# EEZ_DIB_MCU_r1B4.net
KiCad netlist of a schematic drawn in EAGLE
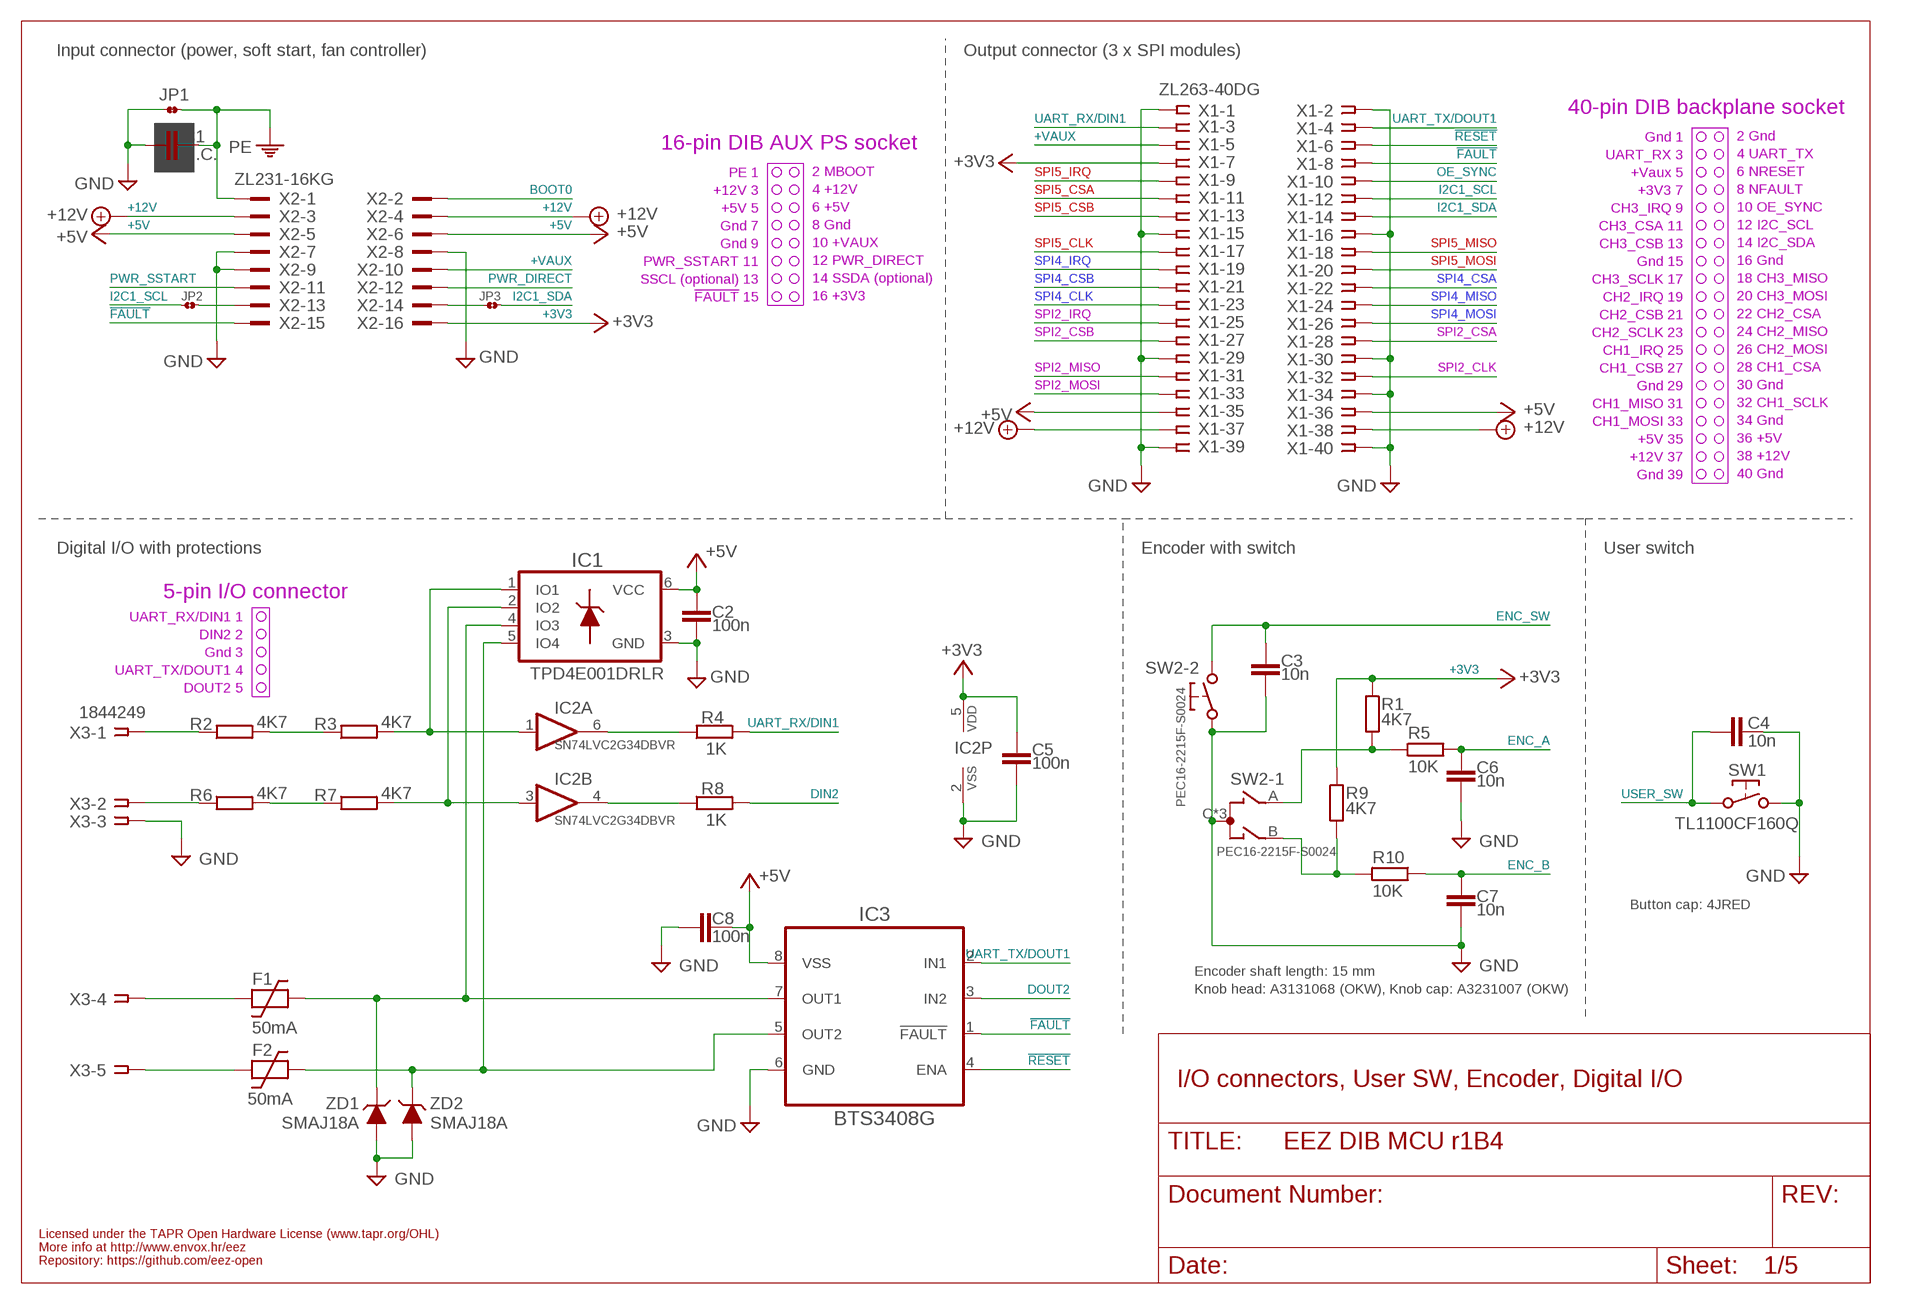
[diagram p0: schematic, sheet 1]
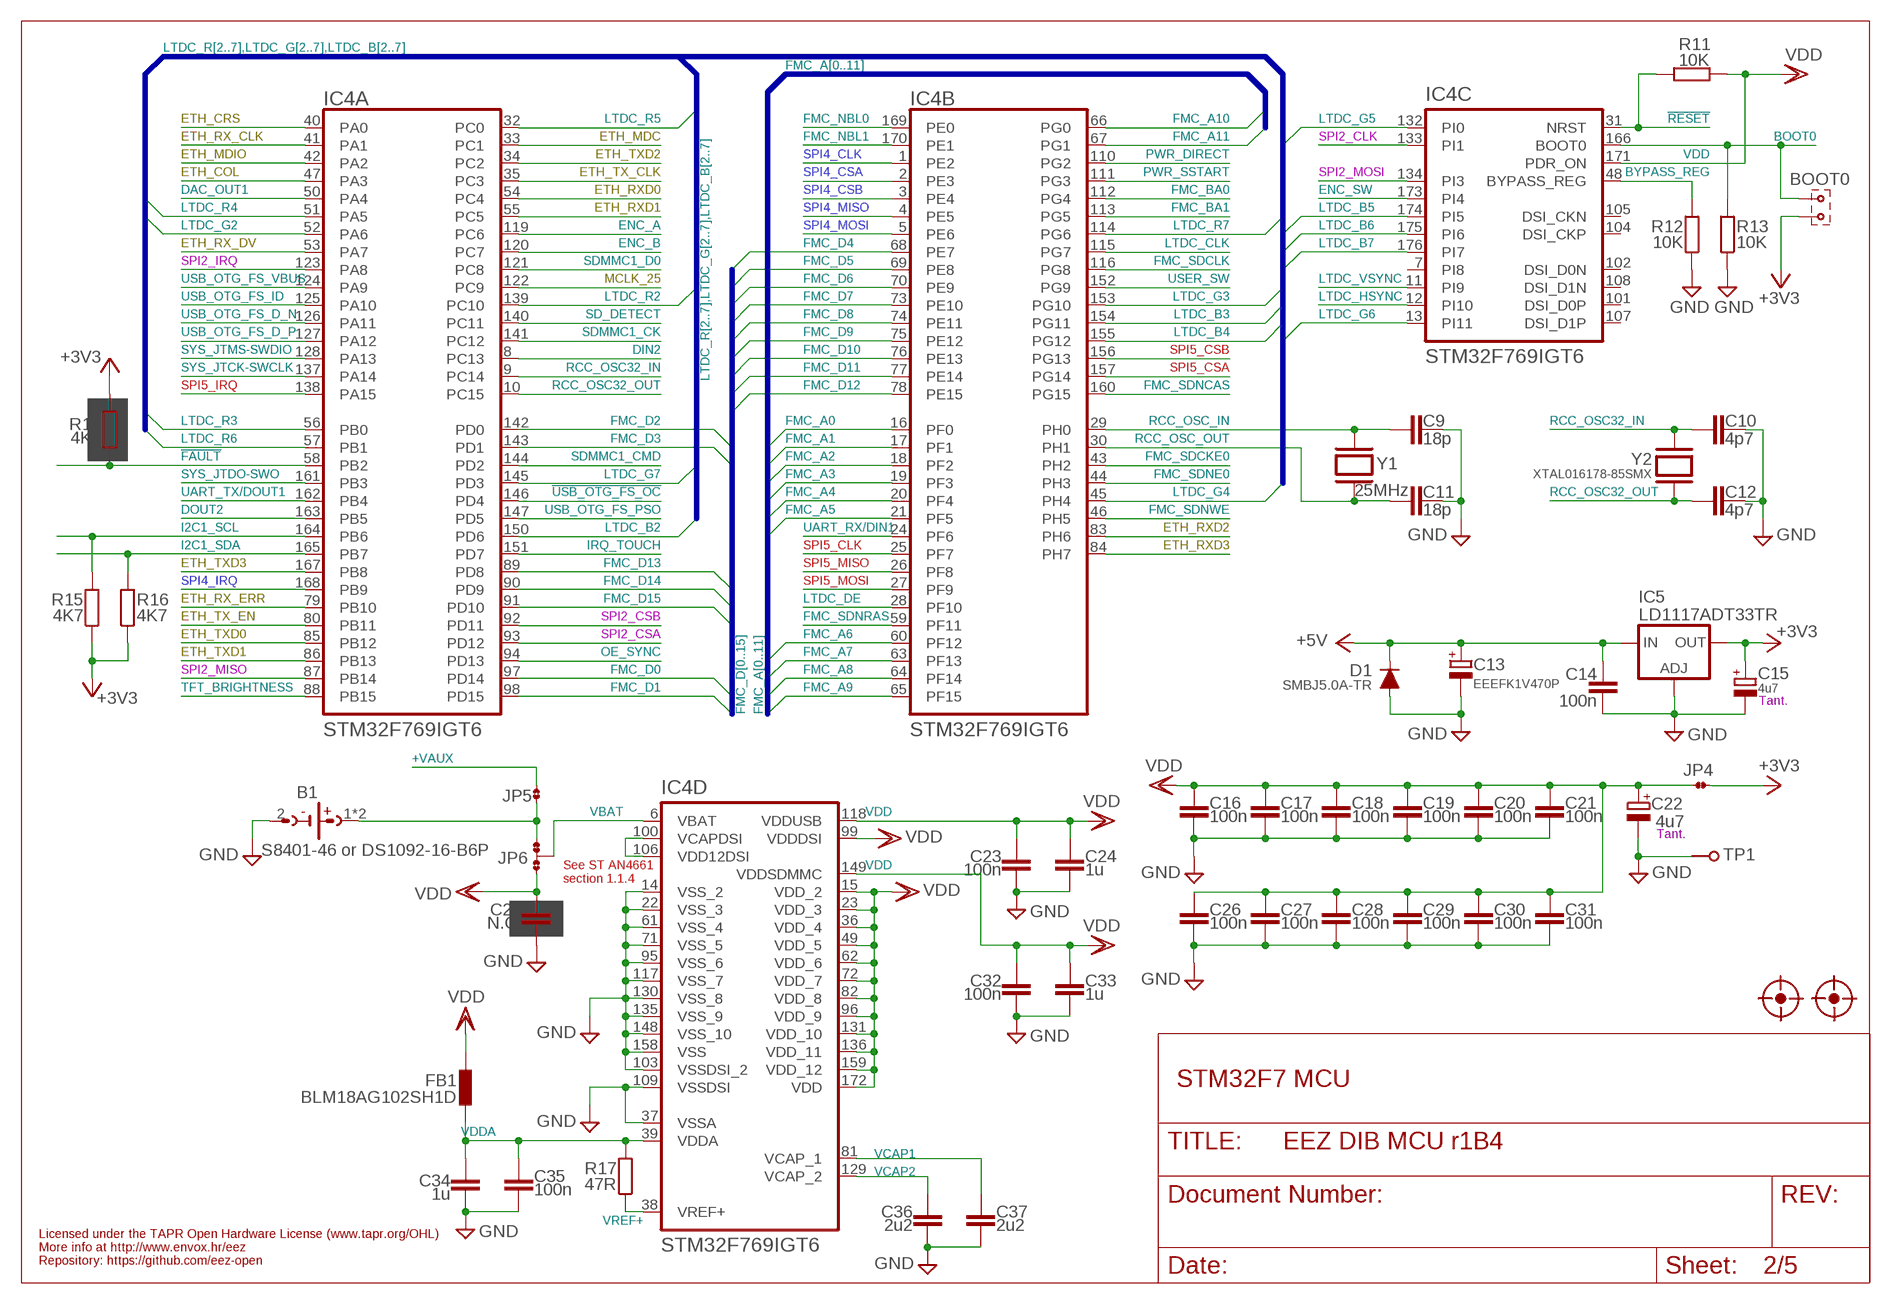
[diagram p1: schematic, sheet 2]
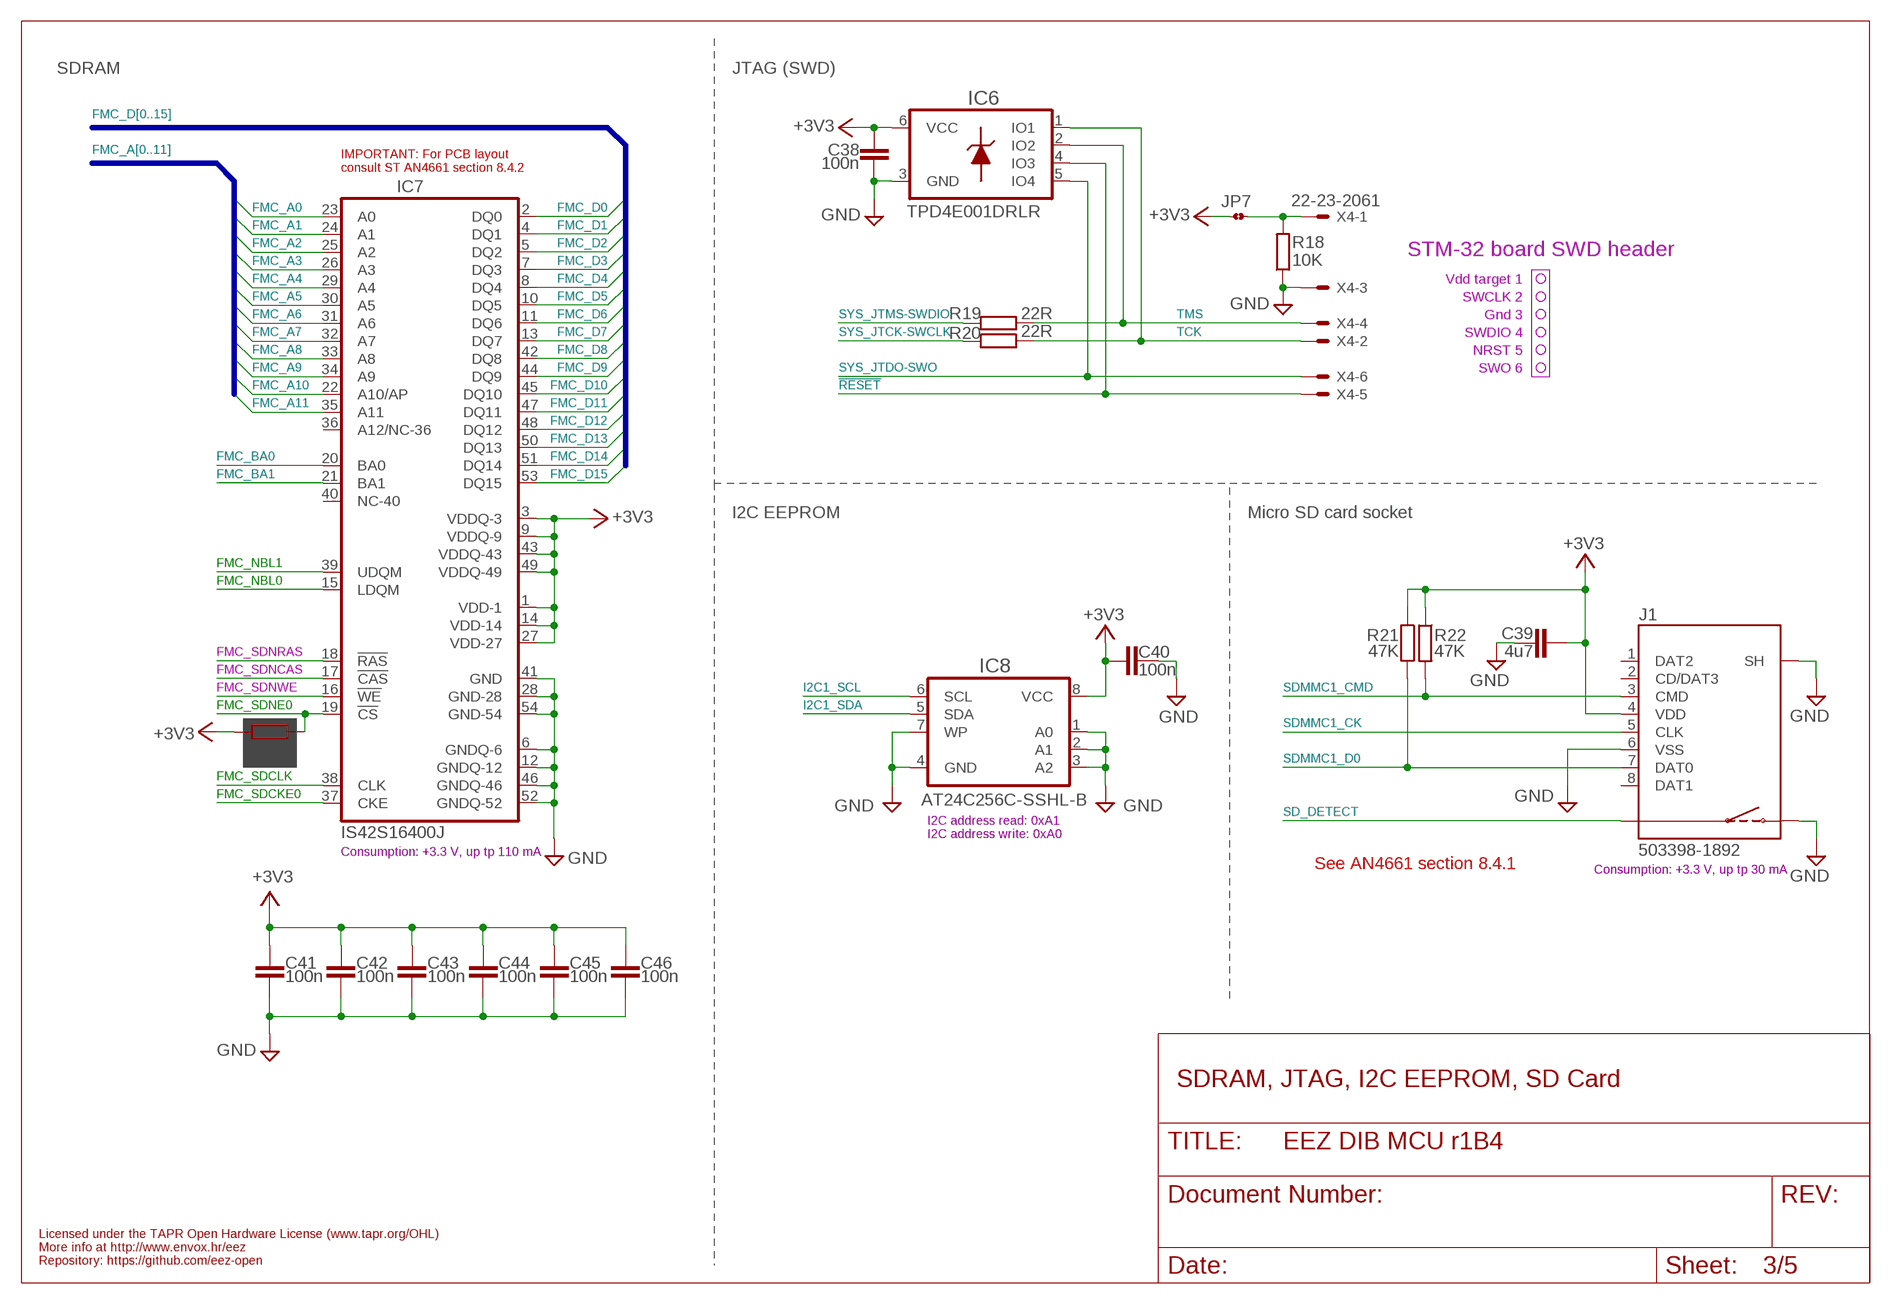
[diagram p2: schematic, sheet 3]
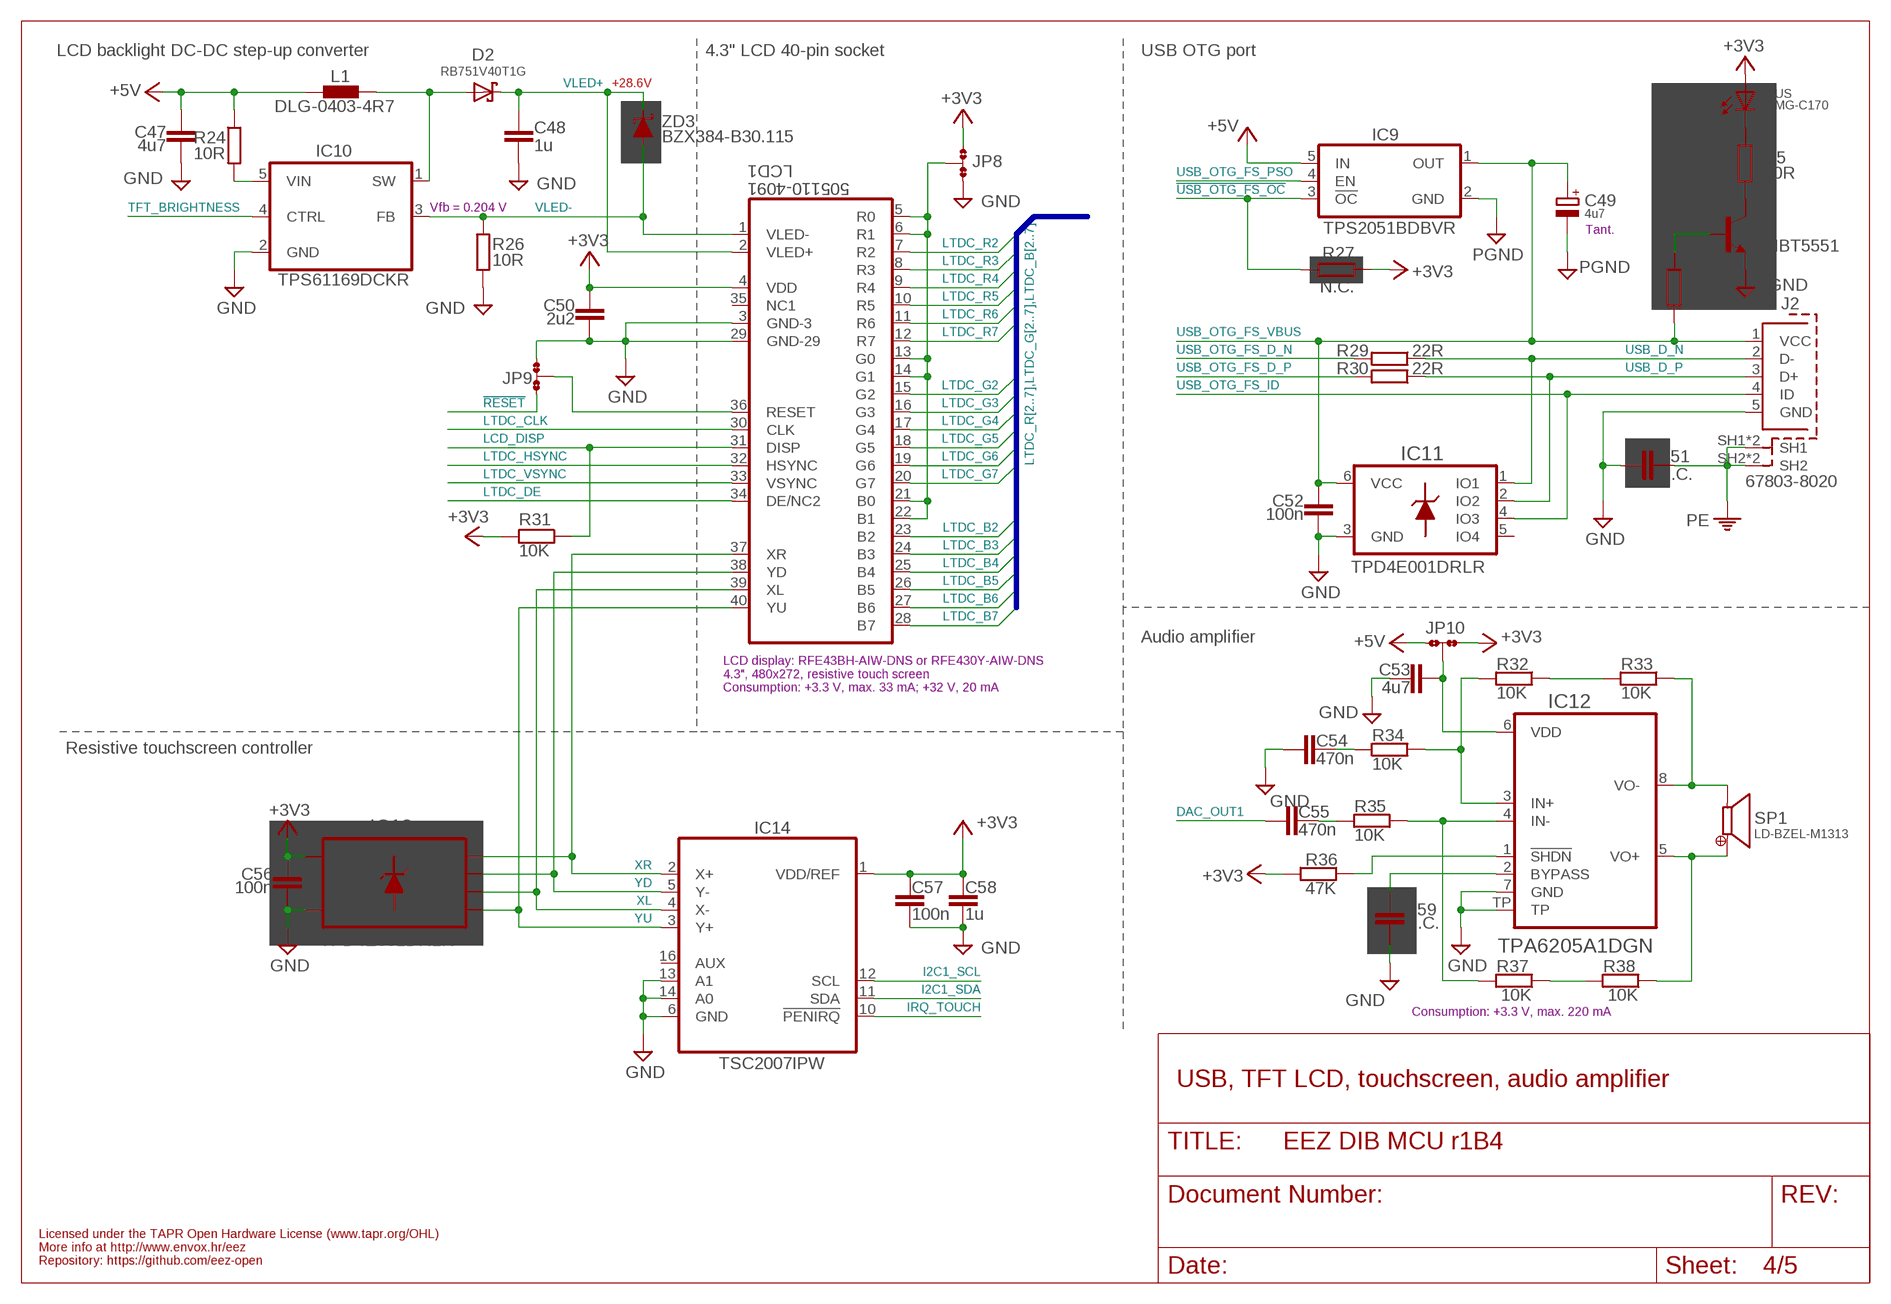
[diagram p3: schematic, sheet 4]
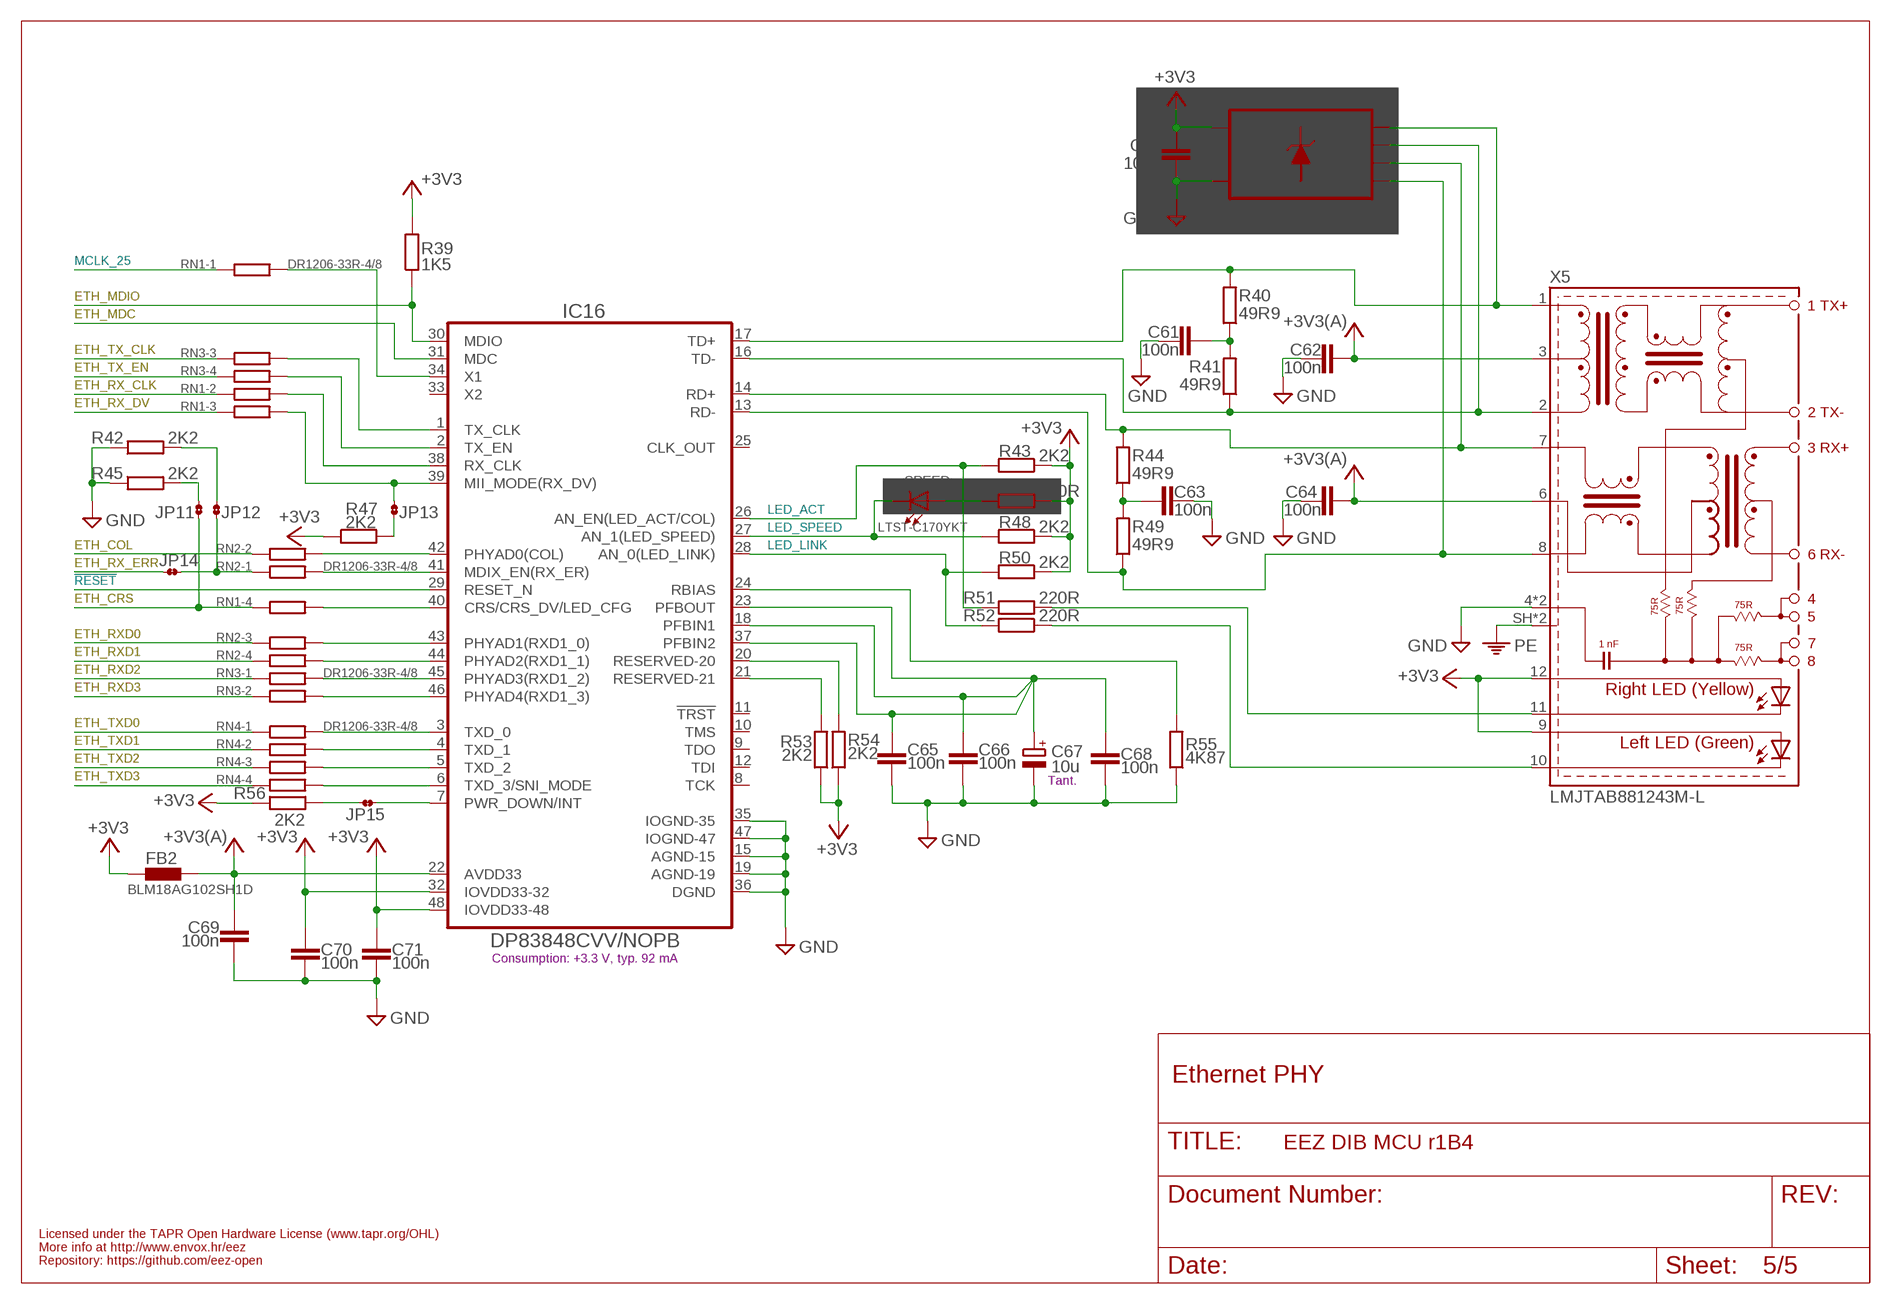
[diagram p4: schematic, sheet 5]

(export (version "E")
  (design (tool "Eeschema 10.0.6"))
  (components
    (comp (ref "C38")
      (value "100n")
      (footprint "eagle-import:C0603")
      (libsource (lib "eagle-import") (part "C-EUC0603"))
    )
    (comp (ref "C39")
      (value "4u7")
      (footprint "eagle-import:C1206")
      (libsource (lib "eagle-import") (part "C-EUC1206"))
    )
    (comp (ref "C40")
      (value "100n")
      (footprint "eagle-import:C0603")
      (libsource (lib "eagle-import") (part "C-EUC0603"))
    )
    (comp (ref "C41")
      (value "100n")
      (footprint "eagle-import:C0603")
      (libsource (lib "eagle-import") (part "C-EUC0603"))
    )
    (comp (ref "C42")
      (value "100n")
      (footprint "eagle-import:C0603")
      (libsource (lib "eagle-import") (part "C-EUC0603"))
    )
    (comp (ref "C43")
      (value "100n")
      (footprint "eagle-import:C0603")
      (libsource (lib "eagle-import") (part "C-EUC0603"))
    )
    (comp (ref "C44")
      (value "100n")
      (footprint "eagle-import:C0603")
      (libsource (lib "eagle-import") (part "C-EUC0603"))
    )
    (comp (ref "C45")
      (value "100n")
      (footprint "eagle-import:C0603")
      (libsource (lib "eagle-import") (part "C-EUC0603"))
    )
    (comp (ref "C46")
      (value "100n")
      (footprint "eagle-import:C0603")
      (libsource (lib "eagle-import") (part "C-EUC0603"))
    )
    (comp (ref "IC6")
      (value "TPD4E001DRLR")
      (footprint "eagle-import:DRL6")
      (libsource (lib "eagle-import") (part "TPD4E001-DRL"))
    )
    (comp (ref "IC7")
      (value "IS42S16400J")
      (footprint "eagle-import:TSOPII-54")
      (libsource (lib "eagle-import") (part "IS42S16400"))
    )
    (comp (ref "IC8")
      (value "AT24C256C-SSHL-B")
      (footprint "eagle-import:SOIC127P600X173-8N")
      (libsource (lib "eagle-import") (part "AT24CXXSOIC8"))
    )
    (comp (ref "J1")
      (value "503398-1892")
      (footprint "eagle-import:5033981892")
      (libsource (lib "eagle-import") (part "5033981892"))
    )
    (comp (ref "JP7")
      (value "JP2-CUT")
      (footprint "eagle-import:JP2-CUT")
      (libsource (lib "eagle-import") (part "JP2-CUT"))
    )
    (comp (ref "R18")
      (value "10K")
      (footprint "eagle-import:R0805")
      (libsource (lib "eagle-import") (part "R-EU_R0805"))
    )
    (comp (ref "R19")
      (value "22R")
      (footprint "eagle-import:R0805")
      (libsource (lib "eagle-import") (part "R-EU_R0805"))
    )
    (comp (ref "R20")
      (value "22R")
      (footprint "eagle-import:R0805")
      (libsource (lib "eagle-import") (part "R-EU_R0805"))
    )
    (comp (ref "R21")
      (value "47K")
      (footprint "eagle-import:R0805")
      (libsource (lib "eagle-import") (part "R-EU_R0805"))
    )
    (comp (ref "R22")
      (value "47K")
      (footprint "eagle-import:R0805")
      (libsource (lib "eagle-import") (part "R-EU_R0805"))
    )
    (comp (ref "R23")
      (value "N.C.")
      (footprint "eagle-import:R0805")
      (libsource (lib "eagle-import") (part "R-EU_R0805"))
    )
    (comp (ref "X4")
      (value "22-23-2061")
      (footprint "eagle-import:22-23-2061")
      (fields (field (name "MF") "MOLEX"))
      (libsource (lib "eagle-import") (part "22-23-2061"))
    )
    (comp (ref "B1")
      (value "S8401-46 or DS1092-16-B6P")
      (footprint "eagle-import:S8401-46")
      (libsource (lib "eagle-import") (part "CELL_BATTERYVERT"))
    )
    (comp (ref "BOOT0")
      (value "JUMPER-2PIN-2MM")
      (footprint "eagle-import:2MM-2")
      (libsource (lib "eagle-import") (part "JUMPER-2PIN-2MM"))
    )
    (comp (ref "C9")
      (value "18p")
      (footprint "eagle-import:C0603")
      (libsource (lib "eagle-import") (part "C-EUC0603"))
    )
    (comp (ref "C10")
      (value "4p7")
      (footprint "eagle-import:C0603")
      (libsource (lib "eagle-import") (part "C-EUC0603"))
    )
    (comp (ref "C11")
      (value "18p")
      (footprint "eagle-import:C0603")
      (libsource (lib "eagle-import") (part "C-EUC0603"))
    )
    (comp (ref "C12")
      (value "4p7")
      (footprint "eagle-import:C0603")
      (libsource (lib "eagle-import") (part "C-EUC0603"))
    )
    (comp (ref "C13")
      (value "EEEFK1V470P")
      (footprint "eagle-import:CAPAE660X610N")
      (libsource (lib "eagle-import") (part "ECAPPANASONIC_H"))
    )
    (comp (ref "C14")
      (value "100n")
      (footprint "eagle-import:C0603")
      (libsource (lib "eagle-import") (part "C-EUC0603"))
    )
    (comp (ref "C15")
      (value "4u7")
      (footprint "eagle-import:EC1206")
      (libsource (lib "eagle-import") (part "ECAP1206"))
    )
    (comp (ref "C16")
      (value "100n")
      (footprint "eagle-import:C0603")
      (libsource (lib "eagle-import") (part "C-EUC0603"))
    )
    (comp (ref "C17")
      (value "100n")
      (footprint "eagle-import:C0603")
      (libsource (lib "eagle-import") (part "C-EUC0603"))
    )
    (comp (ref "C18")
      (value "100n")
      (footprint "eagle-import:C0603")
      (libsource (lib "eagle-import") (part "C-EUC0603"))
    )
    (comp (ref "C19")
      (value "100n")
      (footprint "eagle-import:C0603")
      (libsource (lib "eagle-import") (part "C-EUC0603"))
    )
    (comp (ref "C20")
      (value "100n")
      (footprint "eagle-import:C0603")
      (libsource (lib "eagle-import") (part "C-EUC0603"))
    )
    (comp (ref "C21")
      (value "100n")
      (footprint "eagle-import:C0603")
      (libsource (lib "eagle-import") (part "C-EUC0603"))
    )
    (comp (ref "C22")
      (value "4u7")
      (footprint "eagle-import:EC1206")
      (libsource (lib "eagle-import") (part "ECAP1206"))
    )
    (comp (ref "C23")
      (value "100n")
      (footprint "eagle-import:C0603")
      (libsource (lib "eagle-import") (part "C-EUC0603"))
    )
    (comp (ref "C24")
      (value "1u")
      (footprint "eagle-import:C0805")
      (libsource (lib "eagle-import") (part "C-EUC0805"))
    )
    (comp (ref "C25")
      (value "N.C.")
      (footprint "eagle-import:C0603")
      (libsource (lib "eagle-import") (part "C-EUC0603"))
    )
    (comp (ref "C26")
      (value "100n")
      (footprint "eagle-import:C0603")
      (libsource (lib "eagle-import") (part "C-EUC0603"))
    )
    (comp (ref "C27")
      (value "100n")
      (footprint "eagle-import:C0603")
      (libsource (lib "eagle-import") (part "C-EUC0603"))
    )
    (comp (ref "C28")
      (value "100n")
      (footprint "eagle-import:C0603")
      (libsource (lib "eagle-import") (part "C-EUC0603"))
    )
    (comp (ref "C29")
      (value "100n")
      (footprint "eagle-import:C0603")
      (libsource (lib "eagle-import") (part "C-EUC0603"))
    )
    (comp (ref "C30")
      (value "100n")
      (footprint "eagle-import:C0603")
      (libsource (lib "eagle-import") (part "C-EUC0603"))
    )
    (comp (ref "C31")
      (value "100n")
      (footprint "eagle-import:C0603")
      (libsource (lib "eagle-import") (part "C-EUC0603"))
    )
    (comp (ref "C32")
      (value "100n")
      (footprint "eagle-import:C0603")
      (libsource (lib "eagle-import") (part "C-EUC0603"))
    )
    (comp (ref "C33")
      (value "1u")
      (footprint "eagle-import:C0805")
      (libsource (lib "eagle-import") (part "C-EUC0805"))
    )
    (comp (ref "C34")
      (value "1u")
      (footprint "eagle-import:C0805")
      (libsource (lib "eagle-import") (part "C-EUC0805"))
    )
    (comp (ref "C35")
      (value "100n")
      (footprint "eagle-import:C0603")
      (libsource (lib "eagle-import") (part "C-EUC0603"))
    )
    (comp (ref "C36")
      (value "2u2")
      (footprint "eagle-import:C0805")
      (libsource (lib "eagle-import") (part "C-EUC0805"))
    )
    (comp (ref "C37")
      (value "2u2")
      (footprint "eagle-import:C0805")
      (libsource (lib "eagle-import") (part "C-EUC0805"))
    )
    (comp (ref "D1")
      (value "SMBJ5.0A-TR")
      (footprint "eagle-import:DO214AA")
      (libsource (lib "eagle-import") (part "DIODEDO214AA"))
    )
    (comp (ref "FB1")
      (value "BLM18AG102SH1D")
      (footprint "eagle-import:BEAD0603")
      (libsource (lib "eagle-import") (part "FERRITE_BEAD0603"))
    )
    (comp (ref "FM1")
      (value "FIDUCIAL")
      (footprint "eagle-import:FIDUCIAL")
      (libsource (lib "eagle-import") (part "FIDUCIAL"))
    )
    (comp (ref "FM2")
      (value "FIDUCIAL")
      (footprint "eagle-import:FIDUCIAL")
      (libsource (lib "eagle-import") (part "FIDUCIAL"))
    )
    (comp (ref "IC4")
      (value "STM32F769IGT6")
      (footprint "eagle-import:LQFP-176_24X24MM")
      (fields
        (field (name "MANUFACTURER_PART_NUMBER") "stm32f769ixt")
        (field (name "COPYRIGHT") "Copyright C 2016 Accelerated Designs. All rights reserved")
      )
      (libsource (lib "eagle-import") (part "STM32F769IXT"))
    )
    (comp (ref "IC5")
      (value "LD1117ADT33TR")
      (footprint "eagle-import:DPACK")
      (libsource (lib "eagle-import") (part "LD117A?DT33TR"))
    )
    (comp (ref "JP4")
      (value "JP2-NOCUT")
      (footprint "eagle-import:JP2-NOCUT")
      (libsource (lib "eagle-import") (part "JP2-NOCUT"))
    )
    (comp (ref "JP5")
      (value "JP2-CUT")
      (footprint "eagle-import:JP2-CUT")
      (libsource (lib "eagle-import") (part "JP2-CUT"))
    )
    (comp (ref "JP6")
      (value "JP3-CUT")
      (footprint "eagle-import:JP3-CUT")
      (libsource (lib "eagle-import") (part "JP3-CUT"))
    )
    (comp (ref "R11")
      (value "10K")
      (footprint "eagle-import:R0805")
      (libsource (lib "eagle-import") (part "R-EU_R0805"))
    )
    (comp (ref "R12")
      (value "10K")
      (footprint "eagle-import:R0805")
      (libsource (lib "eagle-import") (part "R-EU_R0805"))
    )
    (comp (ref "R13")
      (value "10K")
      (footprint "eagle-import:R0805")
      (libsource (lib "eagle-import") (part "R-EU_R0805"))
    )
    (comp (ref "R14")
      (value "4K7")
      (footprint "eagle-import:R0805")
      (libsource (lib "eagle-import") (part "R-EU_R0805"))
    )
    (comp (ref "R15")
      (value "4K7")
      (footprint "eagle-import:R0805")
      (libsource (lib "eagle-import") (part "R-EU_R0805"))
    )
    (comp (ref "R16")
      (value "4K7")
      (footprint "eagle-import:R0805")
      (libsource (lib "eagle-import") (part "R-EU_R0805"))
    )
    (comp (ref "R17")
      (value "47R")
      (footprint "eagle-import:R0805")
      (libsource (lib "eagle-import") (part "R-EU_R0805"))
    )
    (comp (ref "TP1")
      (value "PCB_TEST_TABSHIELD")
      (footprint "eagle-import:PCB_SHIELD_TAB")
      (libsource (lib "eagle-import") (part "PCB_TEST_TABSHIELD"))
    )
    (comp (ref "Y1")
      (value "25MHz")
      (footprint "eagle-import:HC-49_4H")
      (libsource (lib "eagle-import") (part "XTALSMD"))
    )
    (comp (ref "Y2")
      (value "XTAL016178-85SMX")
      (footprint "eagle-import:85SMX")
      (libsource (lib "eagle-import") (part "XTAL85SMX"))
    )
    (comp (ref "C60")
      (value "100n")
      (footprint "eagle-import:C0603")
      (libsource (lib "eagle-import") (part "C-EUC0603"))
    )
    (comp (ref "C61")
      (value "100n")
      (footprint "eagle-import:C0603")
      (libsource (lib "eagle-import") (part "C-EUC0603"))
    )
    (comp (ref "C62")
      (value "100n")
      (footprint "eagle-import:C0603")
      (libsource (lib "eagle-import") (part "C-EUC0603"))
    )
    (comp (ref "C63")
      (value "100n")
      (footprint "eagle-import:C0603")
      (libsource (lib "eagle-import") (part "C-EUC0603"))
    )
    (comp (ref "C64")
      (value "100n")
      (footprint "eagle-import:C0603")
      (libsource (lib "eagle-import") (part "C-EUC0603"))
    )
    (comp (ref "C65")
      (value "100n")
      (footprint "eagle-import:C0603")
      (libsource (lib "eagle-import") (part "C-EUC0603"))
    )
    (comp (ref "C66")
      (value "100n")
      (footprint "eagle-import:C0603")
      (libsource (lib "eagle-import") (part "C-EUC0603"))
    )
    (comp (ref "C67")
      (value "10u")
      (footprint "eagle-import:EC1206")
      (libsource (lib "eagle-import") (part "ECAP1206"))
    )
    (comp (ref "C68")
      (value "100n")
      (footprint "eagle-import:C0603")
      (libsource (lib "eagle-import") (part "C-EUC0603"))
    )
    (comp (ref "C69")
      (value "100n")
      (footprint "eagle-import:C0603")
      (libsource (lib "eagle-import") (part "C-EUC0603"))
    )
    (comp (ref "C70")
      (value "100n")
      (footprint "eagle-import:C0603")
      (libsource (lib "eagle-import") (part "C-EUC0603"))
    )
    (comp (ref "C71")
      (value "100n")
      (footprint "eagle-import:C0603")
      (libsource (lib "eagle-import") (part "C-EUC0603"))
    )
    (comp (ref "FB2")
      (value "BLM18AG102SH1D")
      (footprint "eagle-import:BEAD0603")
      (libsource (lib "eagle-import") (part "FERRITE_BEAD0603"))
    )
    (comp (ref "IC15")
      (value "TPD4E001DRLR")
      (footprint "eagle-import:DRL6")
      (libsource (lib "eagle-import") (part "TPD4E001-DRL"))
    )
    (comp (ref "IC16")
      (value "DP83848CVV/NOPB")
      (footprint "eagle-import:PT48")
      (libsource (lib "eagle-import") (part "DP83848CVV/NOPB"))
    )
    (comp (ref "JP11")
      (value "JP2-CUT")
      (footprint "eagle-import:JP2-CUT")
      (libsource (lib "eagle-import") (part "JP2-CUT"))
    )
    (comp (ref "JP12")
      (value "JP2-CUT")
      (footprint "eagle-import:JP2-CUT")
      (libsource (lib "eagle-import") (part "JP2-CUT"))
    )
    (comp (ref "JP13")
      (value "JP2-CUT")
      (footprint "eagle-import:JP2-CUT")
      (libsource (lib "eagle-import") (part "JP2-CUT"))
    )
    (comp (ref "JP14")
      (value "JP2-NOCUT")
      (footprint "eagle-import:JP2-NOCUT")
      (libsource (lib "eagle-import") (part "JP2-NOCUT"))
    )
    (comp (ref "JP15")
      (value "JP2-NOCUT")
      (footprint "eagle-import:JP2-NOCUT")
      (libsource (lib "eagle-import") (part "JP2-NOCUT"))
    )
    (comp (ref "R39")
      (value "1K5")
      (footprint "eagle-import:R0805")
      (libsource (lib "eagle-import") (part "R-EU_R0805"))
    )
    (comp (ref "R40")
      (value "49R9")
      (footprint "eagle-import:R0805")
      (libsource (lib "eagle-import") (part "R-EU_R0805"))
    )
    (comp (ref "R41")
      (value "49R9")
      (footprint "eagle-import:R0805")
      (libsource (lib "eagle-import") (part "R-EU_R0805"))
    )
    (comp (ref "R42")
      (value "2K2")
      (footprint "eagle-import:R0805")
      (libsource (lib "eagle-import") (part "R-EU_R0805"))
    )
    (comp (ref "R43")
      (value "2K2")
      (footprint "eagle-import:R0805")
      (libsource (lib "eagle-import") (part "R-EU_R0805"))
    )
    (comp (ref "R44")
      (value "49R9")
      (footprint "eagle-import:R0805")
      (libsource (lib "eagle-import") (part "R-EU_R0805"))
    )
    (comp (ref "R45")
      (value "2K2")
      (footprint "eagle-import:R0805")
      (libsource (lib "eagle-import") (part "R-EU_R0805"))
    )
    (comp (ref "R46")
      (value "220R")
      (footprint "eagle-import:R0805")
      (libsource (lib "eagle-import") (part "R-EU_R0805"))
    )
    (comp (ref "R47")
      (value "2K2")
      (footprint "eagle-import:R0805")
      (libsource (lib "eagle-import") (part "R-EU_R0805"))
    )
    (comp (ref "R48")
      (value "2K2")
      (footprint "eagle-import:R0805")
      (libsource (lib "eagle-import") (part "R-EU_R0805"))
    )
    (comp (ref "R49")
      (value "49R9")
      (footprint "eagle-import:R0805")
      (libsource (lib "eagle-import") (part "R-EU_R0805"))
    )
    (comp (ref "R50")
      (value "2K2")
      (footprint "eagle-import:R0805")
      (libsource (lib "eagle-import") (part "R-EU_R0805"))
    )
    (comp (ref "R51")
      (value "220R")
      (footprint "eagle-import:R0805")
      (libsource (lib "eagle-import") (part "R-EU_R0805"))
    )
    (comp (ref "R52")
      (value "220R")
      (footprint "eagle-import:R0805")
      (libsource (lib "eagle-import") (part "R-EU_R0805"))
    )
    (comp (ref "R53")
      (value "2K2")
      (footprint "eagle-import:R0805")
      (libsource (lib "eagle-import") (part "R-EU_R0805"))
    )
    (comp (ref "R54")
      (value "2K2")
      (footprint "eagle-import:R0805")
      (libsource (lib "eagle-import") (part "R-EU_R0805"))
    )
    (comp (ref "R55")
      (value "4K87")
      (footprint "eagle-import:R0805")
      (libsource (lib "eagle-import") (part "R-EU_R0805"))
    )
    (comp (ref "R56")
      (value "2K2")
      (footprint "eagle-import:R0805")
      (libsource (lib "eagle-import") (part "R-EU_R0805"))
    )
    (comp (ref "RN1")
      (value "DR1206-33R-4/8")
      (footprint "eagle-import:CAY16")
      (libsource (lib "eagle-import") (part "R_ARRAY4"))
    )
    (comp (ref "RN2")
      (value "DR1206-33R-4/8")
      (footprint "eagle-import:CAY16")
      (libsource (lib "eagle-import") (part "R_ARRAY4"))
    )
    (comp (ref "RN3")
      (value "DR1206-33R-4/8")
      (footprint "eagle-import:CAY16")
      (libsource (lib "eagle-import") (part "R_ARRAY4"))
    )
    (comp (ref "RN4")
      (value "DR1206-33R-4/8")
      (footprint "eagle-import:CAY16")
      (libsource (lib "eagle-import") (part "R_ARRAY4"))
    )
    (comp (ref "SPEED")
      (value "LTST-C170YKT")
      (footprint "eagle-import:LED_0805")
      (libsource (lib "eagle-import") (part "LED0805"))
    )
    (comp (ref "X5")
      (value "LMJTAB881243M-L")
      (footprint "eagle-import:RJ45-TRAFO-LED")
      (libsource (lib "eagle-import") (part "RJ45-TRAFO-LED"))
    )
    (comp (ref "C47")
      (value "4u7")
      (footprint "eagle-import:C1206")
      (libsource (lib "eagle-import") (part "C-EUC1206"))
    )
    (comp (ref "C48")
      (value "1u")
      (footprint "eagle-import:C0805")
      (libsource (lib "eagle-import") (part "C-EUC0805"))
    )
    (comp (ref "C49")
      (value "4u7")
      (footprint "eagle-import:EC1206")
      (libsource (lib "eagle-import") (part "ECAP1206"))
    )
    (comp (ref "C50")
      (value "2u2")
      (footprint "eagle-import:C0805")
      (libsource (lib "eagle-import") (part "C-EUC0805"))
    )
    (comp (ref "C51")
      (value "N.C.")
      (footprint "eagle-import:C1210")
      (libsource (lib "eagle-import") (part "C-EUC1210"))
    )
    (comp (ref "C52")
      (value "100n")
      (footprint "eagle-import:C0603")
      (libsource (lib "eagle-import") (part "C-EUC0603"))
    )
    (comp (ref "C53")
      (value "4u7")
      (footprint "eagle-import:C1206")
      (libsource (lib "eagle-import") (part "C-EUC1206"))
    )
    (comp (ref "C54")
      (value "470n")
      (footprint "eagle-import:C0805")
      (libsource (lib "eagle-import") (part "C-EUC0805"))
    )
    (comp (ref "C55")
      (value "470n")
      (footprint "eagle-import:C0805")
      (libsource (lib "eagle-import") (part "C-EUC0805"))
    )
    (comp (ref "C56")
      (value "100n")
      (footprint "eagle-import:C0603")
      (libsource (lib "eagle-import") (part "C-EUC0603"))
    )
    (comp (ref "C57")
      (value "100n")
      (footprint "eagle-import:C0603")
      (libsource (lib "eagle-import") (part "C-EUC0603"))
    )
    (comp (ref "C58")
      (value "1u")
      (footprint "eagle-import:C0805")
      (libsource (lib "eagle-import") (part "C-EUC0805"))
    )
    (comp (ref "C59")
      (value "N.C.")
      (footprint "eagle-import:C0805")
      (libsource (lib "eagle-import") (part "C-EUC0805"))
    )
    (comp (ref "D2")
      (value "RB751V40T1G")
      (footprint "eagle-import:SOD323-R")
      (libsource (lib "eagle-import") (part "SCHOTTKYSOD-323R"))
    )
    (comp (ref "IC9")
      (value "TPS2051BDBVR")
      (footprint "eagle-import:DBV5")
      (libsource (lib "eagle-import") (part "TPS2051B"))
    )
    (comp (ref "IC10")
      (value "TPS61169DCKR")
      (footprint "eagle-import:DCK5")
      (fields (field (name "MANUFACTURER") "Texas Instruments"))
      (libsource (lib "eagle-import") (part "TPS61169DCKR"))
    )
    (comp (ref "IC11")
      (value "TPD4E001DRLR")
      (footprint "eagle-import:DRL6")
      (libsource (lib "eagle-import") (part "TPD4E001-DRL"))
    )
    (comp (ref "IC12")
      (value "TPA6205A1DGN")
      (footprint "eagle-import:SOP65P490X110-9N")
      (libsource (lib "eagle-import") (part "TPA6205"))
    )
    (comp (ref "IC13")
      (value "TPD4E001DRLR")
      (footprint "eagle-import:DRL6")
      (libsource (lib "eagle-import") (part "TPD4E001-DRL"))
    )
    (comp (ref "IC14")
      (value "TSC2007IPW")
      (footprint "eagle-import:PW(R-PDSO-G16)")
      (libsource (lib "eagle-import") (part "TSC2007IPW"))
    )
    (comp (ref "J2")
      (value "67803-8020")
      (footprint "eagle-import:678038020")
      (libsource (lib "eagle-import") (part "678038020"))
    )
    (comp (ref "JP8")
      (value "JP3-CUT")
      (footprint "eagle-import:JP3-CUT")
      (libsource (lib "eagle-import") (part "JP3-CUT"))
    )
    (comp (ref "JP9")
      (value "JP3-CUT")
      (footprint "eagle-import:JP3-CUT")
      (libsource (lib "eagle-import") (part "JP3-CUT"))
    )
    (comp (ref "JP10")
      (value "JP3-CUT")
      (footprint "eagle-import:JP3-CUT")
      (libsource (lib "eagle-import") (part "JP3-CUT"))
    )
    (comp (ref "L1")
      (value "DLG-0403-4R7")
      (footprint "eagle-import:DE0403")
      (libsource (lib "eagle-import") (part "DE0403"))
    )
    (comp (ref "LCD1")
      (value "505110-4091")
      (footprint "eagle-import:FPC_40")
      (libsource (lib "eagle-import") (part "RFE430Y-AIW-DNS"))
    )
    (comp (ref "Q1")
      (value "MMBT5551")
      (footprint "eagle-import:SOT23-BEC")
      (libsource (lib "eagle-import") (part "-NPN-SOT23-BECMMBT5551LT1"))
    )
    (comp (ref "R24")
      (value "10R")
      (footprint "eagle-import:R0805")
      (libsource (lib "eagle-import") (part "R-EU_R0805"))
    )
    (comp (ref "R25")
      (value "330R")
      (footprint "eagle-import:R0805")
      (libsource (lib "eagle-import") (part "R-EU_R0805"))
    )
    (comp (ref "R26")
      (value "10R")
      (footprint "eagle-import:R0805")
      (libsource (lib "eagle-import") (part "R-EU_R0805"))
    )
    (comp (ref "R27")
      (value "N.C.")
      (footprint "eagle-import:R0805")
      (libsource (lib "eagle-import") (part "R-EU_R0805"))
    )
    (comp (ref "R28")
      (value "47K")
      (footprint "eagle-import:R0805")
      (libsource (lib "eagle-import") (part "R-EU_R0805"))
    )
    (comp (ref "R29")
      (value "22R")
      (footprint "eagle-import:R0805")
      (libsource (lib "eagle-import") (part "R-EU_R0805"))
    )
    (comp (ref "R30")
      (value "22R")
      (footprint "eagle-import:R0805")
      (libsource (lib "eagle-import") (part "R-EU_R0805"))
    )
    (comp (ref "R31")
      (value "10K")
      (footprint "eagle-import:R0805")
      (libsource (lib "eagle-import") (part "R-EU_R0805"))
    )
    (comp (ref "R32")
      (value "10K")
      (footprint "eagle-import:R0805")
      (libsource (lib "eagle-import") (part "R-EU_R0805"))
    )
    (comp (ref "R33")
      (value "10K")
      (footprint "eagle-import:R0805")
      (libsource (lib "eagle-import") (part "R-EU_R0805"))
    )
    (comp (ref "R34")
      (value "10K")
      (footprint "eagle-import:R0805")
      (libsource (lib "eagle-import") (part "R-EU_R0805"))
    )
    (comp (ref "R35")
      (value "10K")
      (footprint "eagle-import:R0805")
      (libsource (lib "eagle-import") (part "R-EU_R0805"))
    )
    (comp (ref "R36")
      (value "47K")
      (footprint "eagle-import:R0805")
      (libsource (lib "eagle-import") (part "R-EU_R0805"))
    )
    (comp (ref "R37")
      (value "10K")
      (footprint "eagle-import:R0805")
      (libsource (lib "eagle-import") (part "R-EU_R0805"))
    )
    (comp (ref "R38")
      (value "10K")
      (footprint "eagle-import:R0805")
      (libsource (lib "eagle-import") (part "R-EU_R0805"))
    )
    (comp (ref "SP1")
      (value "LD-BZEL-M1313")
      (footprint "eagle-import:LD-BZEL-M1313")
      (libsource (lib "eagle-import") (part "LD-BZEL-M1313"))
    )
    (comp (ref "VBUS")
      (value "HSMG-C170")
      (footprint "eagle-import:LED_0805")
      (libsource (lib "eagle-import") (part "LED0805"))
    )
    (comp (ref "ZD3")
      (value "BZX384-B30.115")
      (footprint "eagle-import:SOD323-W")
      (libsource (lib "eagle-import") (part "ZENER-DIODESOD323"))
    )
    (comp (ref "C1")
      (value "N.C.")
      (footprint "eagle-import:C1210")
      (libsource (lib "eagle-import") (part "C-EUC1210"))
    )
    (comp (ref "C2")
      (value "100n")
      (footprint "eagle-import:C0603")
      (libsource (lib "eagle-import") (part "C-EUC0603"))
    )
    (comp (ref "C3")
      (value "10n")
      (footprint "eagle-import:C0805")
      (libsource (lib "eagle-import") (part "C-EUC0805"))
    )
    (comp (ref "C4")
      (value "10n")
      (footprint "eagle-import:C0805")
      (libsource (lib "eagle-import") (part "C-EUC0805"))
    )
    (comp (ref "C5")
      (value "100n")
      (footprint "eagle-import:C0603")
      (libsource (lib "eagle-import") (part "C-EUC0603"))
    )
    (comp (ref "C6")
      (value "10n")
      (footprint "eagle-import:C0805")
      (libsource (lib "eagle-import") (part "C-EUC0805"))
    )
    (comp (ref "C7")
      (value "10n")
      (footprint "eagle-import:C0805")
      (libsource (lib "eagle-import") (part "C-EUC0805"))
    )
    (comp (ref "C8")
      (value "100n")
      (footprint "eagle-import:C0603")
      (libsource (lib "eagle-import") (part "C-EUC0603"))
    )
    (comp (ref "F1")
      (value "50mA")
      (footprint "eagle-import:F1210")
      (libsource (lib "eagle-import") (part "FUSE_RESETTABLE21210"))
    )
    (comp (ref "F2")
      (value "50mA")
      (footprint "eagle-import:F1210")
      (libsource (lib "eagle-import") (part "FUSE_RESETTABLE21210"))
    )
    (comp (ref "IC1")
      (value "TPD4E001DRLR")
      (footprint "eagle-import:DRL6")
      (libsource (lib "eagle-import") (part "TPD4E001-DRL"))
    )
    (comp (ref "IC2")
      (value "SN74LVC2G34DBVR")
      (footprint "eagle-import:DBV6")
      (libsource (lib "eagle-import") (part "SN74LVC2G34DBVR"))
    )
    (comp (ref "IC3")
      (value "BTS3408G")
      (footprint "eagle-import:SOIC127P600X173-8N")
      (libsource (lib "eagle-import") (part "BTS3408G"))
    )
    (comp (ref "JP1")
      (value "JP2-NOCUT")
      (footprint "eagle-import:JP2-NOCUT")
      (libsource (lib "eagle-import") (part "JP2-NOCUT"))
    )
    (comp (ref "JP2")
      (value "JP2-CUT")
      (footprint "eagle-import:JP2-CUT")
      (libsource (lib "eagle-import") (part "JP2-CUT"))
    )
    (comp (ref "JP3")
      (value "JP2-CUT")
      (footprint "eagle-import:JP2-CUT")
      (libsource (lib "eagle-import") (part "JP2-CUT"))
    )
    (comp (ref "R1")
      (value "4K7")
      (footprint "eagle-import:R0805")
      (libsource (lib "eagle-import") (part "R-EU_R0805"))
    )
    (comp (ref "R2")
      (value "4K7")
      (footprint "eagle-import:R0805")
      (libsource (lib "eagle-import") (part "R-EU_R0805"))
    )
    (comp (ref "R3")
      (value "4K7")
      (footprint "eagle-import:R0805")
      (libsource (lib "eagle-import") (part "R-EU_R0805"))
    )
    (comp (ref "R4")
      (value "1K")
      (footprint "eagle-import:R0805")
      (libsource (lib "eagle-import") (part "R-EU_R0805"))
    )
    (comp (ref "R5")
      (value "10K")
      (footprint "eagle-import:R0805")
      (libsource (lib "eagle-import") (part "R-EU_R0805"))
    )
    (comp (ref "R6")
      (value "4K7")
      (footprint "eagle-import:R0805")
      (libsource (lib "eagle-import") (part "R-EU_R0805"))
    )
    (comp (ref "R7")
      (value "4K7")
      (footprint "eagle-import:R0805")
      (libsource (lib "eagle-import") (part "R-EU_R0805"))
    )
    (comp (ref "R8")
      (value "1K")
      (footprint "eagle-import:R0805")
      (libsource (lib "eagle-import") (part "R-EU_R0805"))
    )
    (comp (ref "R9")
      (value "4K7")
      (footprint "eagle-import:R0805")
      (libsource (lib "eagle-import") (part "R-EU_R0805"))
    )
    (comp (ref "R10")
      (value "10K")
      (footprint "eagle-import:R0805")
      (libsource (lib "eagle-import") (part "R-EU_R0805"))
    )
    (comp (ref "SW1")
      (value "TL1100CF160Q")
      (footprint "eagle-import:TL1100C")
      (libsource (lib "eagle-import") (part "TL1100C"))
    )
    (comp (ref "SW2")
      (value "PEC16-2215F-S0024")
      (footprint "eagle-import:PEC16-2215F")
      (libsource (lib "eagle-import") (part "ENCODER_SW-PEC16"))
    )
    (comp (ref "X1")
      (value "ZL263-40DG")
      (footprint "eagle-import:ZL263-40DG")
      (libsource (lib "eagle-import") (part "ZL263-40DG"))
    )
    (comp (ref "X2")
      (value "ZL231-16KG")
      (footprint "eagle-import:ML16L")
      (libsource (lib "eagle-import") (part "IDC-16PIN-ANGLED"))
    )
    (comp (ref "X3")
      (value "1844249")
      (footprint "eagle-import:MC1,5_5-G-3,5")
      (libsource (lib "eagle-import") (part "MC1,5/5-G-3,5"))
    )
    (comp (ref "ZD1")
      (value "SMAJ18A")
      (footprint "eagle-import:DO214AC")
      (libsource (lib "eagle-import") (part "PSMAXX"))
    )
    (comp (ref "ZD2")
      (value "SMAJ18A")
      (footprint "eagle-import:DO214AC")
      (libsource (lib "eagle-import") (part "PSMAXX"))
    )
  )
  (nets
    (net (code "1") (name "+3V3") (class "Default")
      (node (ref "BOOT0") (pin "2") (pinfunction "2_2") (pintype "passive"))
      (node (ref "C15") (pin "+") (pinfunction "+_+") (pintype "passive"))
      (node (ref "C38") (pin "1") (pinfunction "1_1") (pintype "passive"))
      (node (ref "C39") (pin "1") (pinfunction "1_1") (pintype "passive"))
      (node (ref "C40") (pin "2") (pinfunction "2_2") (pintype "passive"))
      (node (ref "C41") (pin "1") (pinfunction "1_1") (pintype "passive"))
      (node (ref "C42") (pin "1") (pinfunction "1_1") (pintype "passive"))
      (node (ref "C43") (pin "1") (pinfunction "1_1") (pintype "passive"))
      (node (ref "C44") (pin "1") (pinfunction "1_1") (pintype "passive"))
      (node (ref "C45") (pin "1") (pinfunction "1_1") (pintype "passive"))
      (node (ref "C46") (pin "1") (pinfunction "1_1") (pintype "passive"))
      (node (ref "C5") (pin "1") (pinfunction "1_1") (pintype "passive"))
      (node (ref "C50") (pin "1") (pinfunction "1_1") (pintype "passive"))
      (node (ref "C56") (pin "2") (pinfunction "2_2") (pintype "passive"))
      (node (ref "C57") (pin "2") (pinfunction "2_2") (pintype "passive"))
      (node (ref "C58") (pin "2") (pinfunction "2_2") (pintype "passive"))
      (node (ref "C60") (pin "1") (pinfunction "1_1") (pintype "passive"))
      (node (ref "C70") (pin "1") (pinfunction "1_1") (pintype "passive"))
      (node (ref "C71") (pin "1") (pinfunction "1_1") (pintype "passive"))
      (node (ref "FB2") (pin "P$1") (pinfunction "1_P$1") (pintype "passive"))
      (node (ref "IC13") (pin "6") (pinfunction "VCC_6") (pintype "passive"))
      (node (ref "IC14") (pin "1") (pinfunction "VDD/REF_1") (pintype "passive"))
      (node (ref "IC15") (pin "6") (pinfunction "VCC_6") (pintype "passive"))
      (node (ref "IC16") (pin "32") (pinfunction "IOVDD33-32_32") (pintype "power_in"))
      (node (ref "IC16") (pin "48") (pinfunction "IOVDD33-48_48") (pintype "power_in"))
      (node (ref "IC2") (pin "5") (pinfunction "VDD_5") (pintype "power_in"))
      (node (ref "IC5") (pin "4") (pinfunction "OUT_4") (pintype "passive"))
      (node (ref "IC6") (pin "6") (pinfunction "VCC_6") (pintype "passive"))
      (node (ref "IC7") (pin "1") (pinfunction "VDD-1_1") (pintype "power_in"))
      (node (ref "IC7") (pin "14") (pinfunction "VDD-14_14") (pintype "power_in"))
      (node (ref "IC7") (pin "27") (pinfunction "VDD-27_27") (pintype "power_in"))
      (node (ref "IC7") (pin "3") (pinfunction "VDDQ-3_3") (pintype "power_in"))
      (node (ref "IC7") (pin "43") (pinfunction "VDDQ-43_43") (pintype "power_in"))
      (node (ref "IC7") (pin "49") (pinfunction "VDDQ-49_49") (pintype "power_in"))
      (node (ref "IC7") (pin "9") (pinfunction "VDDQ-9_9") (pintype "power_in"))
      (node (ref "IC8") (pin "8") (pinfunction "VCC_8") (pintype "power_in"))
      (node (ref "J1") (pin "4") (pinfunction "VDD_4") (pintype "power_in"))
      (node (ref "JP10") (pin "NC") (pinfunction "NC_NC") (pintype "passive"))
      (node (ref "JP4") (pin "2") (pinfunction "2_2") (pintype "passive"))
      (node (ref "JP7") (pin "1") (pinfunction "1_1") (pintype "passive"))
      (node (ref "JP8") (pin "NO") (pinfunction "NO_NO") (pintype "passive"))
      (node (ref "LCD1") (pin "4") (pinfunction "VDD_4") (pintype "power_in"))
      (node (ref "R1") (pin "1") (pinfunction "1_1") (pintype "passive"))
      (node (ref "R14") (pin "1") (pinfunction "1_1") (pintype "passive"))
      (node (ref "R15") (pin "1") (pinfunction "1_1") (pintype "passive"))
      (node (ref "R16") (pin "1") (pinfunction "1_1") (pintype "passive"))
      (node (ref "R21") (pin "1") (pinfunction "1_1") (pintype "passive"))
      (node (ref "R22") (pin "1") (pinfunction "1_1") (pintype "passive"))
      (node (ref "R23") (pin "1") (pinfunction "1_1") (pintype "passive"))
      (node (ref "R27") (pin "2") (pinfunction "2_2") (pintype "passive"))
      (node (ref "R31") (pin "2") (pinfunction "2_2") (pintype "passive"))
      (node (ref "R36") (pin "2") (pinfunction "2_2") (pintype "passive"))
      (node (ref "R39") (pin "2") (pinfunction "2_2") (pintype "passive"))
      (node (ref "R43") (pin "1") (pinfunction "1_1") (pintype "passive"))
      (node (ref "R46") (pin "1") (pinfunction "1_1") (pintype "passive"))
      (node (ref "R47") (pin "1") (pinfunction "1_1") (pintype "passive"))
      (node (ref "R48") (pin "1") (pinfunction "1_1") (pintype "passive"))
      (node (ref "R50") (pin "1") (pinfunction "1_1") (pintype "passive"))
      (node (ref "R53") (pin "1") (pinfunction "1_1") (pintype "passive"))
      (node (ref "R54") (pin "1") (pinfunction "1_1") (pintype "passive"))
      (node (ref "R56") (pin "1") (pinfunction "1_1") (pintype "passive"))
      (node (ref "R9") (pin "1") (pinfunction "1_1") (pintype "passive"))
      (node (ref "VBUS") (pin "A") (pinfunction "A_A") (pintype "passive"))
      (node (ref "X1") (pin "7") (pinfunction "1_7") (pintype "passive"))
      (node (ref "X2") (pin "16") (pinfunction "1_16") (pintype "passive"))
      (node (ref "X5") (pin "12") (pinfunction "YELLOW_A_12") (pintype "passive"))
      (node (ref "X5") (pin "9") (pinfunction "GREEN-A_9") (pintype "passive"))
    )
    (net (code "2") (name "+3V3(A)") (class "Default")
      (node (ref "C62") (pin "2") (pinfunction "2_2") (pintype "passive"))
      (node (ref "C64") (pin "2") (pinfunction "2_2") (pintype "passive"))
      (node (ref "C69") (pin "1") (pinfunction "1_1") (pintype "passive"))
      (node (ref "FB2") (pin "P$2") (pinfunction "2_P$2") (pintype "passive"))
      (node (ref "IC16") (pin "22") (pinfunction "AVDD33_22") (pintype "power_in"))
      (node (ref "X5") (pin "3") (pinfunction "CT_3") (pintype "input"))
      (node (ref "X5") (pin "6") (pinfunction "CR_6") (pintype "input"))
    )
    (net (code "3") (name "+5V") (class "Default")
      (node (ref "C13") (pin "1") (pinfunction "+_1") (pintype "passive"))
      (node (ref "C14") (pin "1") (pinfunction "1_1") (pintype "passive"))
      (node (ref "C2") (pin "1") (pinfunction "1_1") (pintype "passive"))
      (node (ref "C47") (pin "1") (pinfunction "1_1") (pintype "passive"))
      (node (ref "C8") (pin "2") (pinfunction "2_2") (pintype "passive"))
      (node (ref "D1") (pin "C") (pinfunction "C_C") (pintype "passive"))
      (node (ref "IC1") (pin "6") (pinfunction "VCC_6") (pintype "passive"))
      (node (ref "IC3") (pin "8") (pinfunction "VSS_8") (pintype "passive"))
      (node (ref "IC5") (pin "3") (pinfunction "IN_3") (pintype "input"))
      (node (ref "IC9") (pin "5") (pinfunction "IN_5") (pintype "input"))
      (node (ref "JP10") (pin "NO") (pinfunction "NO_NO") (pintype "passive"))
      (node (ref "L1") (pin "1") (pinfunction "1_1") (pintype "passive"))
      (node (ref "R24") (pin "1") (pinfunction "1_1") (pintype "passive"))
      (node (ref "X1") (pin "35") (pinfunction "1_35") (pintype "passive"))
      (node (ref "X1") (pin "36") (pinfunction "1_36") (pintype "passive"))
      (node (ref "X2") (pin "5") (pinfunction "1_5") (pintype "passive"))
      (node (ref "X2") (pin "6") (pinfunction "1_6") (pintype "passive"))
    )
    (net (code "4") (name "+12V") (class "Default")
      (node (ref "X1") (pin "37") (pinfunction "1_37") (pintype "passive"))
      (node (ref "X1") (pin "38") (pinfunction "1_38") (pintype "passive"))
      (node (ref "X2") (pin "3") (pinfunction "1_3") (pintype "passive"))
      (node (ref "X2") (pin "4") (pinfunction "1_4") (pintype "passive"))
    )
    (net (code "5") (name "+VAUX") (class "Default")
      (node (ref "JP5") (pin "2") (pinfunction "2_2") (pintype "passive"))
      (node (ref "X1") (pin "5") (pinfunction "1_5") (pintype "passive"))
      (node (ref "X2") (pin "10") (pinfunction "1_10") (pintype "passive"))
    )
    (net (code "12") (name "BOOT0") (class "Default")
      (node (ref "BOOT0") (pin "1") (pinfunction "1_1") (pintype "passive"))
      (node (ref "IC4") (pin "166") (pinfunction "BOOT0_166") (pintype "input"))
      (node (ref "R13") (pin "2") (pinfunction "2_2") (pintype "passive"))
      (node (ref "X2") (pin "2") (pinfunction "1_2") (pintype "passive"))
    )
    (net (code "13") (name "BYPASS_REG") (class "Default")
      (node (ref "IC4") (pin "48") (pinfunction "BYPASS_REG_48") (pintype "input"))
      (node (ref "R12") (pin "2") (pinfunction "2_2") (pintype "passive"))
    )
    (net (code "14") (name "DAC_OUT1") (class "Default")
      (node (ref "C55") (pin "2") (pinfunction "2_2") (pintype "passive"))
      (node (ref "IC4") (pin "50") (pinfunction "PA4_50") (pintype "bidirectional"))
    )
    (net (code "15") (name "DIN2") (class "Default")
      (node (ref "IC4") (pin "8") (pinfunction "PC13_8") (pintype "bidirectional"))
      (node (ref "R8") (pin "2") (pinfunction "2_2") (pintype "passive"))
    )
    (net (code "16") (name "DOUT2") (class "Default")
      (node (ref "IC3") (pin "3") (pinfunction "IN2_3") (pintype "input"))
      (node (ref "IC4") (pin "163") (pinfunction "PB5_163") (pintype "bidirectional"))
    )
    (net (code "17") (name "ENC_A") (class "Default")
      (node (ref "C6") (pin "2") (pinfunction "2_2") (pintype "passive"))
      (node (ref "IC4") (pin "119") (pinfunction "PC6_119") (pintype "bidirectional"))
      (node (ref "R5") (pin "1") (pinfunction "1_1") (pintype "passive"))
    )
    (net (code "18") (name "ENC_B") (class "Default")
      (node (ref "C7") (pin "1") (pinfunction "1_1") (pintype "passive"))
      (node (ref "IC4") (pin "120") (pinfunction "PC7_120") (pintype "bidirectional"))
      (node (ref "R10") (pin "1") (pinfunction "1_1") (pintype "passive"))
    )
    (net (code "19") (name "ENC_SW") (class "Default")
      (node (ref "C3") (pin "2") (pinfunction "2_2") (pintype "passive"))
      (node (ref "IC4") (pin "173") (pinfunction "PI4_173") (pintype "bidirectional"))
      (node (ref "SW2") (pin "E") (pinfunction "2_E") (pintype "passive"))
    )
    (net (code "20") (name "ETH_COL") (class "Default")
      (node (ref "IC4") (pin "47") (pinfunction "PA3_47") (pintype "bidirectional"))
      (node (ref "RN2") (pin "2") (pinfunction "1_2") (pintype "passive"))
    )
    (net (code "21") (name "ETH_CRS") (class "Default")
      (node (ref "IC4") (pin "40") (pinfunction "PA0_40") (pintype "bidirectional"))
      (node (ref "JP11") (pin "1") (pinfunction "1_1") (pintype "passive"))
      (node (ref "RN1") (pin "4") (pinfunction "1_4") (pintype "passive"))
    )
    (net (code "22") (name "ETH_MDC") (class "Default")
      (node (ref "IC16") (pin "31") (pinfunction "MDC_31") (pintype "input"))
      (node (ref "IC4") (pin "33") (pinfunction "PC1_33") (pintype "bidirectional"))
    )
    (net (code "23") (name "ETH_MDIO") (class "Default")
      (node (ref "IC16") (pin "30") (pinfunction "MDIO_30") (pintype "bidirectional"))
      (node (ref "IC4") (pin "42") (pinfunction "PA2_42") (pintype "bidirectional"))
      (node (ref "R39") (pin "1") (pinfunction "1_1") (pintype "passive"))
    )
    (net (code "24") (name "ETH_RXD0") (class "Default")
      (node (ref "IC4") (pin "54") (pinfunction "PC4_54") (pintype "bidirectional"))
      (node (ref "RN2") (pin "3") (pinfunction "1_3") (pintype "passive"))
    )
    (net (code "25") (name "ETH_RXD1") (class "Default")
      (node (ref "IC4") (pin "55") (pinfunction "PC5_55") (pintype "bidirectional"))
      (node (ref "RN2") (pin "4") (pinfunction "1_4") (pintype "passive"))
    )
    (net (code "26") (name "ETH_RXD2") (class "Default")
      (node (ref "IC4") (pin "83") (pinfunction "PH6_83") (pintype "bidirectional"))
      (node (ref "RN3") (pin "1") (pinfunction "1_1") (pintype "passive"))
    )
    (net (code "27") (name "ETH_RXD3") (class "Default")
      (node (ref "IC4") (pin "84") (pinfunction "PH7_84") (pintype "bidirectional"))
      (node (ref "RN3") (pin "2") (pinfunction "1_2") (pintype "passive"))
    )
    (net (code "28") (name "ETH_RX_CLK") (class "Default")
      (node (ref "IC4") (pin "41") (pinfunction "PA1_41") (pintype "bidirectional"))
      (node (ref "RN1") (pin "2") (pinfunction "1_2") (pintype "passive"))
    )
    (net (code "29") (name "ETH_RX_DV") (class "Default")
      (node (ref "IC4") (pin "53") (pinfunction "PA7_53") (pintype "bidirectional"))
      (node (ref "RN1") (pin "3") (pinfunction "1_3") (pintype "passive"))
    )
    (net (code "30") (name "ETH_RX_ERR") (class "Default")
      (node (ref "IC4") (pin "79") (pinfunction "PB10_79") (pintype "bidirectional"))
      (node (ref "JP14") (pin "2") (pinfunction "2_2") (pintype "passive"))
    )
    (net (code "31") (name "ETH_TXD0") (class "Default")
      (node (ref "IC4") (pin "85") (pinfunction "PB12_85") (pintype "bidirectional"))
      (node (ref "RN4") (pin "1") (pinfunction "1_1") (pintype "passive"))
    )
    (net (code "32") (name "ETH_TXD1") (class "Default")
      (node (ref "IC4") (pin "86") (pinfunction "PB13_86") (pintype "bidirectional"))
      (node (ref "RN4") (pin "2") (pinfunction "1_2") (pintype "passive"))
    )
    (net (code "33") (name "ETH_TXD2") (class "Default")
      (node (ref "IC4") (pin "34") (pinfunction "PC2_34") (pintype "bidirectional"))
      (node (ref "RN4") (pin "3") (pinfunction "1_3") (pintype "passive"))
    )
    (net (code "34") (name "ETH_TXD3") (class "Default")
      (node (ref "IC4") (pin "167") (pinfunction "PB8_167") (pintype "bidirectional"))
      (node (ref "RN4") (pin "4") (pinfunction "1_4") (pintype "passive"))
    )
    (net (code "35") (name "ETH_TX_CLK") (class "Default")
      (node (ref "IC4") (pin "35") (pinfunction "PC3_35") (pintype "bidirectional"))
      (node (ref "RN3") (pin "3") (pinfunction "1_3") (pintype "passive"))
    )
    (net (code "36") (name "ETH_TX_EN") (class "Default")
      (node (ref "IC4") (pin "80") (pinfunction "PB11_80") (pintype "bidirectional"))
      (node (ref "RN3") (pin "4") (pinfunction "1_4") (pintype "passive"))
    )
    (net (code "37") (name "FMC_A0") (class "Default")
      (node (ref "IC4") (pin "16") (pinfunction "PF0_16") (pintype "bidirectional"))
      (node (ref "IC7") (pin "23") (pinfunction "A0_23") (pintype "input"))
    )
    (net (code "38") (name "FMC_A1") (class "Default")
      (node (ref "IC4") (pin "17") (pinfunction "PF1_17") (pintype "bidirectional"))
      (node (ref "IC7") (pin "24") (pinfunction "A1_24") (pintype "input"))
    )
    (net (code "39") (name "FMC_A2") (class "Default")
      (node (ref "IC4") (pin "18") (pinfunction "PF2_18") (pintype "bidirectional"))
      (node (ref "IC7") (pin "25") (pinfunction "A2_25") (pintype "input"))
    )
    (net (code "40") (name "FMC_A3") (class "Default")
      (node (ref "IC4") (pin "19") (pinfunction "PF3_19") (pintype "bidirectional"))
      (node (ref "IC7") (pin "26") (pinfunction "A3_26") (pintype "input"))
    )
    (net (code "41") (name "FMC_A4") (class "Default")
      (node (ref "IC4") (pin "20") (pinfunction "PF4_20") (pintype "bidirectional"))
      (node (ref "IC7") (pin "29") (pinfunction "A4_29") (pintype "input"))
    )
    (net (code "42") (name "FMC_A5") (class "Default")
      (node (ref "IC4") (pin "21") (pinfunction "PF5_21") (pintype "bidirectional"))
      (node (ref "IC7") (pin "30") (pinfunction "A5_30") (pintype "input"))
    )
    (net (code "43") (name "FMC_A6") (class "Default")
      (node (ref "IC4") (pin "60") (pinfunction "PF12_60") (pintype "bidirectional"))
      (node (ref "IC7") (pin "31") (pinfunction "A6_31") (pintype "input"))
    )
    (net (code "44") (name "FMC_A7") (class "Default")
      (node (ref "IC4") (pin "63") (pinfunction "PF13_63") (pintype "bidirectional"))
      (node (ref "IC7") (pin "32") (pinfunction "A7_32") (pintype "input"))
    )
    (net (code "45") (name "FMC_A8") (class "Default")
      (node (ref "IC4") (pin "64") (pinfunction "PF14_64") (pintype "bidirectional"))
      (node (ref "IC7") (pin "33") (pinfunction "A8_33") (pintype "input"))
    )
    (net (code "46") (name "FMC_A9") (class "Default")
      (node (ref "IC4") (pin "65") (pinfunction "PF15_65") (pintype "bidirectional"))
      (node (ref "IC7") (pin "34") (pinfunction "A9_34") (pintype "input"))
    )
    (net (code "47") (name "FMC_A10") (class "Default")
      (node (ref "IC4") (pin "66") (pinfunction "PG0_66") (pintype "bidirectional"))
      (node (ref "IC7") (pin "22") (pinfunction "A10/AP_22") (pintype "input"))
    )
    (net (code "48") (name "FMC_A11") (class "Default")
      (node (ref "IC4") (pin "67") (pinfunction "PG1_67") (pintype "bidirectional"))
      (node (ref "IC7") (pin "35") (pinfunction "A11_35") (pintype "input"))
    )
    (net (code "49") (name "FMC_BA0") (class "Default")
      (node (ref "IC4") (pin "112") (pinfunction "PG4_112") (pintype "bidirectional"))
      (node (ref "IC7") (pin "20") (pinfunction "BA0_20") (pintype "input"))
    )
    (net (code "50") (name "FMC_BA1") (class "Default")
      (node (ref "IC4") (pin "113") (pinfunction "PG5_113") (pintype "bidirectional"))
      (node (ref "IC7") (pin "21") (pinfunction "BA1_21") (pintype "input"))
    )
    (net (code "51") (name "FMC_D0") (class "Default")
      (node (ref "IC4") (pin "97") (pinfunction "PD14_97") (pintype "bidirectional"))
      (node (ref "IC7") (pin "2") (pinfunction "DQ0_2") (pintype "bidirectional"))
    )
    (net (code "52") (name "FMC_D1") (class "Default")
      (node (ref "IC4") (pin "98") (pinfunction "PD15_98") (pintype "bidirectional"))
      (node (ref "IC7") (pin "4") (pinfunction "DQ1_4") (pintype "bidirectional"))
    )
    (net (code "53") (name "FMC_D2") (class "Default")
      (node (ref "IC4") (pin "142") (pinfunction "PD0_142") (pintype "bidirectional"))
      (node (ref "IC7") (pin "5") (pinfunction "DQ2_5") (pintype "bidirectional"))
    )
    (net (code "54") (name "FMC_D3") (class "Default")
      (node (ref "IC4") (pin "143") (pinfunction "PD1_143") (pintype "bidirectional"))
      (node (ref "IC7") (pin "7") (pinfunction "DQ3_7") (pintype "bidirectional"))
    )
    (net (code "55") (name "FMC_D4") (class "Default")
      (node (ref "IC4") (pin "68") (pinfunction "PE7_68") (pintype "bidirectional"))
      (node (ref "IC7") (pin "8") (pinfunction "DQ4_8") (pintype "bidirectional"))
    )
    (net (code "56") (name "FMC_D5") (class "Default")
      (node (ref "IC4") (pin "69") (pinfunction "PE8_69") (pintype "bidirectional"))
      (node (ref "IC7") (pin "10") (pinfunction "DQ5_10") (pintype "bidirectional"))
    )
    (net (code "57") (name "FMC_D6") (class "Default")
      (node (ref "IC4") (pin "70") (pinfunction "PE9_70") (pintype "bidirectional"))
      (node (ref "IC7") (pin "11") (pinfunction "DQ6_11") (pintype "bidirectional"))
    )
    (net (code "58") (name "FMC_D7") (class "Default")
      (node (ref "IC4") (pin "73") (pinfunction "PE10_73") (pintype "bidirectional"))
      (node (ref "IC7") (pin "13") (pinfunction "DQ7_13") (pintype "bidirectional"))
    )
    (net (code "59") (name "FMC_D8") (class "Default")
      (node (ref "IC4") (pin "74") (pinfunction "PE11_74") (pintype "bidirectional"))
      (node (ref "IC7") (pin "42") (pinfunction "DQ8_42") (pintype "bidirectional"))
    )
    (net (code "60") (name "FMC_D9") (class "Default")
      (node (ref "IC4") (pin "75") (pinfunction "PE12_75") (pintype "bidirectional"))
      (node (ref "IC7") (pin "44") (pinfunction "DQ9_44") (pintype "bidirectional"))
    )
    (net (code "61") (name "FMC_D10") (class "Default")
      (node (ref "IC4") (pin "76") (pinfunction "PE13_76") (pintype "bidirectional"))
      (node (ref "IC7") (pin "45") (pinfunction "DQ10_45") (pintype "bidirectional"))
    )
    (net (code "62") (name "FMC_D11") (class "Default")
      (node (ref "IC4") (pin "77") (pinfunction "PE14_77") (pintype "bidirectional"))
      (node (ref "IC7") (pin "47") (pinfunction "DQ11_47") (pintype "bidirectional"))
    )
    (net (code "63") (name "FMC_D12") (class "Default")
      (node (ref "IC4") (pin "78") (pinfunction "PE15_78") (pintype "bidirectional"))
      (node (ref "IC7") (pin "48") (pinfunction "DQ12_48") (pintype "bidirectional"))
    )
    (net (code "64") (name "FMC_D13") (class "Default")
      (node (ref "IC4") (pin "89") (pinfunction "PD8_89") (pintype "bidirectional"))
      (node (ref "IC7") (pin "50") (pinfunction "DQ13_50") (pintype "bidirectional"))
    )
    (net (code "65") (name "FMC_D14") (class "Default")
      (node (ref "IC4") (pin "90") (pinfunction "PD9_90") (pintype "bidirectional"))
      (node (ref "IC7") (pin "51") (pinfunction "DQ14_51") (pintype "bidirectional"))
    )
    (net (code "66") (name "FMC_D15") (class "Default")
      (node (ref "IC4") (pin "91") (pinfunction "PD10_91") (pintype "bidirectional"))
      (node (ref "IC7") (pin "53") (pinfunction "DQ15_53") (pintype "bidirectional"))
    )
    (net (code "67") (name "FMC_NBL0") (class "Default")
      (node (ref "IC4") (pin "169") (pinfunction "PE0_169") (pintype "bidirectional"))
      (node (ref "IC7") (pin "15") (pinfunction "LDQM_15") (pintype "input"))
    )
    (net (code "68") (name "FMC_NBL1") (class "Default")
      (node (ref "IC4") (pin "170") (pinfunction "PE1_170") (pintype "bidirectional"))
      (node (ref "IC7") (pin "39") (pinfunction "UDQM_39") (pintype "input"))
    )
    (net (code "69") (name "FMC_SDCKE0") (class "Default")
      (node (ref "IC4") (pin "43") (pinfunction "PH2_43") (pintype "bidirectional"))
      (node (ref "IC7") (pin "37") (pinfunction "CKE_37") (pintype "input"))
    )
    (net (code "70") (name "FMC_SDCLK") (class "Default")
      (node (ref "IC4") (pin "116") (pinfunction "PG8_116") (pintype "bidirectional"))
      (node (ref "IC7") (pin "38") (pinfunction "CLK_38") (pintype "input"))
    )
    (net (code "71") (name "FMC_SDNCAS") (class "Default")
      (node (ref "IC4") (pin "160") (pinfunction "PG15_160") (pintype "bidirectional"))
      (node (ref "IC7") (pin "17") (pinfunction "~{CAS}_17") (pintype "input"))
    )
    (net (code "72") (name "FMC_SDNE0") (class "Default")
      (node (ref "IC4") (pin "44") (pinfunction "PH3_44") (pintype "bidirectional"))
      (node (ref "IC7") (pin "19") (pinfunction "~{CS}_19") (pintype "input"))
      (node (ref "R23") (pin "2") (pinfunction "2_2") (pintype "passive"))
    )
    (net (code "73") (name "FMC_SDNRAS") (class "Default")
      (node (ref "IC4") (pin "59") (pinfunction "PF11_59") (pintype "bidirectional"))
      (node (ref "IC7") (pin "18") (pinfunction "~{RAS}_18") (pintype "input"))
    )
    (net (code "74") (name "FMC_SDNWE") (class "Default")
      (node (ref "IC4") (pin "46") (pinfunction "PH5_46") (pintype "bidirectional"))
      (node (ref "IC7") (pin "16") (pinfunction "~{WE}_16") (pintype "input"))
    )
    (net (code "75") (name "GND") (class "Default")
      (node (ref "B1") (pin "2") (pinfunction "-_2") (pintype "passive"))
      (node (ref "C1") (pin "2") (pinfunction "2_2") (pintype "passive"))
      (node (ref "C10") (pin "2") (pinfunction "2_2") (pintype "passive"))
      (node (ref "C11") (pin "1") (pinfunction "1_1") (pintype "passive"))
      (node (ref "C12") (pin "2") (pinfunction "2_2") (pintype "passive"))
      (node (ref "C13") (pin "2") (pinfunction "-_2") (pintype "passive"))
      (node (ref "C14") (pin "2") (pinfunction "2_2") (pintype "passive"))
      (node (ref "C15") (pin "-") (pinfunction "-_-") (pintype "passive"))
      (node (ref "C16") (pin "2") (pinfunction "2_2") (pintype "passive"))
      (node (ref "C17") (pin "2") (pinfunction "2_2") (pintype "passive"))
      (node (ref "C18") (pin "2") (pinfunction "2_2") (pintype "passive"))
      (node (ref "C19") (pin "2") (pinfunction "2_2") (pintype "passive"))
      (node (ref "C2") (pin "2") (pinfunction "2_2") (pintype "passive"))
      (node (ref "C20") (pin "2") (pinfunction "2_2") (pintype "passive"))
      (node (ref "C21") (pin "2") (pinfunction "2_2") (pintype "passive"))
      (node (ref "C22") (pin "-") (pinfunction "-_-") (pintype "passive"))
      (node (ref "C23") (pin "2") (pinfunction "2_2") (pintype "passive"))
      (node (ref "C24") (pin "2") (pinfunction "2_2") (pintype "passive"))
      (node (ref "C25") (pin "2") (pinfunction "2_2") (pintype "passive"))
      (node (ref "C26") (pin "2") (pinfunction "2_2") (pintype "passive"))
      (node (ref "C27") (pin "2") (pinfunction "2_2") (pintype "passive"))
      (node (ref "C28") (pin "2") (pinfunction "2_2") (pintype "passive"))
      (node (ref "C29") (pin "2") (pinfunction "2_2") (pintype "passive"))
      (node (ref "C3") (pin "1") (pinfunction "1_1") (pintype "passive"))
      (node (ref "C30") (pin "2") (pinfunction "2_2") (pintype "passive"))
      (node (ref "C31") (pin "2") (pinfunction "2_2") (pintype "passive"))
      (node (ref "C32") (pin "2") (pinfunction "2_2") (pintype "passive"))
      (node (ref "C33") (pin "2") (pinfunction "2_2") (pintype "passive"))
      (node (ref "C34") (pin "2") (pinfunction "2_2") (pintype "passive"))
      (node (ref "C35") (pin "2") (pinfunction "2_2") (pintype "passive"))
      (node (ref "C36") (pin "2") (pinfunction "2_2") (pintype "passive"))
      (node (ref "C37") (pin "2") (pinfunction "2_2") (pintype "passive"))
      (node (ref "C38") (pin "2") (pinfunction "2_2") (pintype "passive"))
      (node (ref "C39") (pin "2") (pinfunction "2_2") (pintype "passive"))
      (node (ref "C4") (pin "1") (pinfunction "1_1") (pintype "passive"))
      (node (ref "C40") (pin "1") (pinfunction "1_1") (pintype "passive"))
      (node (ref "C41") (pin "2") (pinfunction "2_2") (pintype "passive"))
      (node (ref "C42") (pin "2") (pinfunction "2_2") (pintype "passive"))
      (node (ref "C43") (pin "2") (pinfunction "2_2") (pintype "passive"))
      (node (ref "C44") (pin "2") (pinfunction "2_2") (pintype "passive"))
      (node (ref "C45") (pin "2") (pinfunction "2_2") (pintype "passive"))
      (node (ref "C46") (pin "2") (pinfunction "2_2") (pintype "passive"))
      (node (ref "C47") (pin "2") (pinfunction "2_2") (pintype "passive"))
      (node (ref "C48") (pin "2") (pinfunction "2_2") (pintype "passive"))
      (node (ref "C49") (pin "-") (pinfunction "-_-") (pintype "passive"))
      (node (ref "C5") (pin "2") (pinfunction "2_2") (pintype "passive"))
      (node (ref "C50") (pin "2") (pinfunction "2_2") (pintype "passive"))
      (node (ref "C51") (pin "2") (pinfunction "2_2") (pintype "passive"))
      (node (ref "C52") (pin "1") (pinfunction "1_1") (pintype "passive"))
      (node (ref "C53") (pin "1") (pinfunction "1_1") (pintype "passive"))
      (node (ref "C54") (pin "2") (pinfunction "2_2") (pintype "passive"))
      (node (ref "C56") (pin "1") (pinfunction "1_1") (pintype "passive"))
      (node (ref "C57") (pin "1") (pinfunction "1_1") (pintype "passive"))
      (node (ref "C58") (pin "1") (pinfunction "1_1") (pintype "passive"))
      (node (ref "C59") (pin "1") (pinfunction "1_1") (pintype "passive"))
      (node (ref "C6") (pin "1") (pinfunction "1_1") (pintype "passive"))
      (node (ref "C60") (pin "2") (pinfunction "2_2") (pintype "passive"))
      (node (ref "C61") (pin "2") (pinfunction "2_2") (pintype "passive"))
      (node (ref "C62") (pin "1") (pinfunction "1_1") (pintype "passive"))
      (node (ref "C63") (pin "2") (pinfunction "2_2") (pintype "passive"))
      (node (ref "C64") (pin "1") (pinfunction "1_1") (pintype "passive"))
      (node (ref "C65") (pin "2") (pinfunction "2_2") (pintype "passive"))
      (node (ref "C66") (pin "2") (pinfunction "2_2") (pintype "passive"))
      (node (ref "C67") (pin "-") (pinfunction "-_-") (pintype "passive"))
      (node (ref "C68") (pin "2") (pinfunction "2_2") (pintype "passive"))
      (node (ref "C69") (pin "2") (pinfunction "2_2") (pintype "passive"))
      (node (ref "C7") (pin "2") (pinfunction "2_2") (pintype "passive"))
      (node (ref "C70") (pin "2") (pinfunction "2_2") (pintype "passive"))
      (node (ref "C71") (pin "2") (pinfunction "2_2") (pintype "passive"))
      (node (ref "C8") (pin "1") (pinfunction "1_1") (pintype "passive"))
      (node (ref "C9") (pin "1") (pinfunction "1_1") (pintype "passive"))
      (node (ref "D1") (pin "A") (pinfunction "A_A") (pintype "passive"))
      (node (ref "IC1") (pin "3") (pinfunction "GND_3") (pintype "power_in"))
      (node (ref "IC10") (pin "2") (pinfunction "GND_2") (pintype "power_in"))
      (node (ref "IC11") (pin "3") (pinfunction "GND_3") (pintype "power_in"))
      (node (ref "IC12") (pin "7") (pinfunction "GND_7") (pintype "passive"))
      (node (ref "IC12") (pin "TP") (pinfunction "TP_TP") (pintype "passive"))
      (node (ref "IC13") (pin "3") (pinfunction "GND_3") (pintype "power_in"))
      (node (ref "IC14") (pin "13") (pinfunction "A1_13") (pintype "input"))
      (node (ref "IC14") (pin "14") (pinfunction "A0_14") (pintype "input"))
      (node (ref "IC14") (pin "6") (pinfunction "GND_6") (pintype "passive"))
      (node (ref "IC15") (pin "3") (pinfunction "GND_3") (pintype "power_in"))
      (node (ref "IC16") (pin "15") (pinfunction "AGND-15_15") (pintype "power_in"))
      (node (ref "IC16") (pin "19") (pinfunction "AGND-19_19") (pintype "power_in"))
      (node (ref "IC16") (pin "35") (pinfunction "IOGND-35_35") (pintype "power_in"))
      (node (ref "IC16") (pin "36") (pinfunction "DGND_36") (pintype "power_in"))
      (node (ref "IC16") (pin "47") (pinfunction "IOGND-47_47") (pintype "power_in"))
      (node (ref "IC2") (pin "2") (pinfunction "VSS_2") (pintype "power_in"))
      (node (ref "IC3") (pin "6") (pinfunction "GND_6") (pintype "passive"))
      (node (ref "IC4") (pin "103") (pinfunction "VSSDSI_2_103") (pintype "power_in"))
      (node (ref "IC4") (pin "109") (pinfunction "VSSDSI_109") (pintype "power_in"))
      (node (ref "IC4") (pin "117") (pinfunction "VSS_7_117") (pintype "power_in"))
      (node (ref "IC4") (pin "130") (pinfunction "VSS_8_130") (pintype "power_in"))
      (node (ref "IC4") (pin "135") (pinfunction "VSS_9_135") (pintype "power_in"))
      (node (ref "IC4") (pin "14") (pinfunction "VSS_2_14") (pintype "power_in"))
      (node (ref "IC4") (pin "148") (pinfunction "VSS_10_148") (pintype "power_in"))
      (node (ref "IC4") (pin "158") (pinfunction "VSS_158") (pintype "power_in"))
      (node (ref "IC4") (pin "22") (pinfunction "VSS_3_22") (pintype "power_in"))
      (node (ref "IC4") (pin "37") (pinfunction "VSSA_37") (pintype "power_in"))
      (node (ref "IC4") (pin "61") (pinfunction "VSS_4_61") (pintype "power_in"))
      (node (ref "IC4") (pin "71") (pinfunction "VSS_5_71") (pintype "power_in"))
      (node (ref "IC4") (pin "95") (pinfunction "VSS_6_95") (pintype "power_in"))
      (node (ref "IC5") (pin "1") (pinfunction "ADJ_1") (pintype "input"))
      (node (ref "IC6") (pin "3") (pinfunction "GND_3") (pintype "power_in"))
      (node (ref "IC7") (pin "12") (pinfunction "GNDQ-12_12") (pintype "power_in"))
      (node (ref "IC7") (pin "28") (pinfunction "GND-28_28") (pintype "power_in"))
      (node (ref "IC7") (pin "41") (pinfunction "GND_41") (pintype "power_in"))
      (node (ref "IC7") (pin "46") (pinfunction "GNDQ-46_46") (pintype "power_in"))
      (node (ref "IC7") (pin "52") (pinfunction "GNDQ-52_52") (pintype "power_in"))
      (node (ref "IC7") (pin "54") (pinfunction "GND-54_54") (pintype "power_in"))
      (node (ref "IC7") (pin "6") (pinfunction "GNDQ-6_6") (pintype "power_in"))
      (node (ref "IC8") (pin "1") (pinfunction "A0_1") (pintype "input"))
      (node (ref "IC8") (pin "2") (pinfunction "A1_2") (pintype "input"))
      (node (ref "IC8") (pin "3") (pinfunction "A2_3") (pintype "input"))
      (node (ref "IC8") (pin "4") (pinfunction "GND_4") (pintype "passive"))
      (node (ref "IC8") (pin "7") (pinfunction "WP_7") (pintype "input"))
      (node (ref "IC9") (pin "2") (pinfunction "GND_2") (pintype "power_in"))
      (node (ref "J1") (pin "6") (pinfunction "VSS_6") (pintype "power_in"))
      (node (ref "J1") (pin "S") (pinfunction "SH_S") (pintype "passive"))
      (node (ref "J1") (pin "SW2") (pinfunction "SW2_SW2") (pintype "passive"))
      (node (ref "J2") (pin "5") (pinfunction "GND_5") (pintype "passive"))
      (node (ref "JP1") (pin "1") (pinfunction "1_1") (pintype "passive"))
      (node (ref "JP8") (pin "NC") (pinfunction "NC_NC") (pintype "passive"))
      (node (ref "JP9") (pin "NC") (pinfunction "NC_NC") (pintype "passive"))
      (node (ref "LCD1") (pin "29") (pinfunction "GND-29_29") (pintype "power_in"))
      (node (ref "LCD1") (pin "3") (pinfunction "GND-3_3") (pintype "power_in"))
      (node (ref "Q1") (pin "E") (pinfunction "E_E") (pintype "passive"))
      (node (ref "R12") (pin "1") (pinfunction "1_1") (pintype "passive"))
      (node (ref "R13") (pin "1") (pinfunction "1_1") (pintype "passive"))
      (node (ref "R18") (pin "1") (pinfunction "1_1") (pintype "passive"))
      (node (ref "R26") (pin "2") (pinfunction "2_2") (pintype "passive"))
      (node (ref "R42") (pin "1") (pinfunction "1_1") (pintype "passive"))
      (node (ref "R45") (pin "1") (pinfunction "1_1") (pintype "passive"))
      (node (ref "R55") (pin "1") (pinfunction "1_1") (pintype "passive"))
      (node (ref "SW1") (pin "2") (pinfunction "2_2") (pintype "passive"))
      (node (ref "SW2") (pin "C") (pinfunction "C_C") (pintype "passive"))
      (node (ref "SW2") (pin "D") (pinfunction "1_D") (pintype "passive"))
      (node (ref "SW2") (pin "GND1") (pinfunction "C_GND1") (pintype "passive"))
      (node (ref "SW2") (pin "GND2") (pinfunction "C_GND2") (pintype "passive"))
      (node (ref "TP1") (pin "1") (pinfunction "P$1_1") (pintype "bidirectional"))
      (node (ref "X1") (pin "1") (pinfunction "1_1") (pintype "passive"))
      (node (ref "X1") (pin "15") (pinfunction "1_15") (pintype "passive"))
      (node (ref "X1") (pin "16") (pinfunction "1_16") (pintype "passive"))
      (node (ref "X1") (pin "2") (pinfunction "1_2") (pintype "passive"))
      (node (ref "X1") (pin "29") (pinfunction "1_29") (pintype "passive"))
      (node (ref "X1") (pin "30") (pinfunction "1_30") (pintype "passive"))
      (node (ref "X1") (pin "34") (pinfunction "1_34") (pintype "passive"))
      (node (ref "X1") (pin "39") (pinfunction "1_39") (pintype "passive"))
      (node (ref "X1") (pin "40") (pinfunction "1_40") (pintype "passive"))
      (node (ref "X2") (pin "7") (pinfunction "1_7") (pintype "passive"))
      (node (ref "X2") (pin "8") (pinfunction "1_8") (pintype "passive"))
      (node (ref "X2") (pin "9") (pinfunction "1_9") (pintype "passive"))
      (node (ref "X3") (pin "3") (pinfunction "1_3") (pintype "passive"))
      (node (ref "X4") (pin "3") (pinfunction "S_3") (pintype "passive"))
      (node (ref "X5") (pin "4") (pinfunction "GND_4") (pintype "passive"))
      (node (ref "X5") (pin "5") (pinfunction "GND_5") (pintype "passive"))
      (node (ref "ZD1") (pin "A") (pinfunction "A_A") (pintype "passive"))
      (node (ref "ZD2") (pin "A") (pinfunction "A_A") (pintype "passive"))
    )
    (net (code "76") (name "I2C1_SCL") (class "Default")
      (node (ref "IC14") (pin "12") (pinfunction "SCL_12") (pintype "bidirectional"))
      (node (ref "IC4") (pin "164") (pinfunction "PB6_164") (pintype "bidirectional"))
      (node (ref "IC8") (pin "6") (pinfunction "SCL_6") (pintype "bidirectional"))
      (node (ref "JP2") (pin "1") (pinfunction "1_1") (pintype "passive"))
      (node (ref "R15") (pin "2") (pinfunction "2_2") (pintype "passive"))
      (node (ref "X1") (pin "12") (pinfunction "1_12") (pintype "passive"))
    )
    (net (code "77") (name "I2C1_SDA") (class "Default")
      (node (ref "IC14") (pin "11") (pinfunction "SDA_11") (pintype "bidirectional"))
      (node (ref "IC4") (pin "165") (pinfunction "PB7_165") (pintype "bidirectional"))
      (node (ref "IC8") (pin "5") (pinfunction "SDA_5") (pintype "bidirectional"))
      (node (ref "JP3") (pin "2") (pinfunction "2_2") (pintype "passive"))
      (node (ref "R16") (pin "2") (pinfunction "2_2") (pintype "passive"))
      (node (ref "X1") (pin "14") (pinfunction "1_14") (pintype "passive"))
    )
    (net (code "78") (name "IRQ_TOUCH") (class "Default")
      (node (ref "IC14") (pin "10") (pinfunction "~{PENIRQ}_10") (pintype "output"))
      (node (ref "IC4") (pin "151") (pinfunction "PD7_151") (pintype "bidirectional"))
    )
    (net (code "79") (name "LCD_DISP") (class "Default")
      (node (ref "LCD1") (pin "31") (pinfunction "DISP_31") (pintype "input"))
      (node (ref "R31") (pin "1") (pinfunction "1_1") (pintype "passive"))
    )
    (net (code "80") (name "LED_ACT") (class "Default")
      (node (ref "IC16") (pin "26") (pinfunction "AN_EN(LED_ACT/COL)_26") (pintype "output"))
      (node (ref "R43") (pin "2") (pinfunction "2_2") (pintype "passive"))
      (node (ref "R51") (pin "2") (pinfunction "2_2") (pintype "passive"))
    )
    (net (code "81") (name "LED_LINK") (class "Default")
      (node (ref "IC16") (pin "28") (pinfunction "AN_0(LED_LINK)_28") (pintype "output"))
      (node (ref "R50") (pin "2") (pinfunction "2_2") (pintype "passive"))
      (node (ref "R52") (pin "2") (pinfunction "2_2") (pintype "passive"))
    )
    (net (code "82") (name "LED_SPEED") (class "Default")
      (node (ref "IC16") (pin "27") (pinfunction "AN_1(LED_SPEED)_27") (pintype "output"))
      (node (ref "R48") (pin "2") (pinfunction "2_2") (pintype "passive"))
      (node (ref "SPEED") (pin "C") (pinfunction "C_C") (pintype "passive"))
    )
    (net (code "83") (name "LTDC_B2") (class "Default")
      (node (ref "IC4") (pin "150") (pinfunction "PD6_150") (pintype "bidirectional"))
      (node (ref "LCD1") (pin "23") (pinfunction "B2_23") (pintype "input"))
    )
    (net (code "84") (name "LTDC_B3") (class "Default")
      (node (ref "IC4") (pin "154") (pinfunction "PG11_154") (pintype "bidirectional"))
      (node (ref "LCD1") (pin "24") (pinfunction "B3_24") (pintype "input"))
    )
    (net (code "85") (name "LTDC_B4") (class "Default")
      (node (ref "IC4") (pin "155") (pinfunction "PG12_155") (pintype "bidirectional"))
      (node (ref "LCD1") (pin "25") (pinfunction "B4_25") (pintype "input"))
    )
    (net (code "86") (name "LTDC_B5") (class "Default")
      (node (ref "IC4") (pin "174") (pinfunction "PI5_174") (pintype "bidirectional"))
      (node (ref "LCD1") (pin "26") (pinfunction "B5_26") (pintype "input"))
    )
    (net (code "87") (name "LTDC_B6") (class "Default")
      (node (ref "IC4") (pin "175") (pinfunction "PI6_175") (pintype "bidirectional"))
      (node (ref "LCD1") (pin "27") (pinfunction "B6_27") (pintype "input"))
    )
    (net (code "88") (name "LTDC_B7") (class "Default")
      (node (ref "IC4") (pin "176") (pinfunction "PI7_176") (pintype "bidirectional"))
      (node (ref "LCD1") (pin "28") (pinfunction "B7_28") (pintype "input"))
    )
    (net (code "89") (name "LTDC_CLK") (class "Default")
      (node (ref "IC4") (pin "115") (pinfunction "PG7_115") (pintype "bidirectional"))
      (node (ref "LCD1") (pin "30") (pinfunction "CLK_30") (pintype "input"))
    )
    (net (code "90") (name "LTDC_DE") (class "Default")
      (node (ref "IC4") (pin "28") (pinfunction "PF10_28") (pintype "bidirectional"))
      (node (ref "LCD1") (pin "34") (pinfunction "DE/NC2_34") (pintype "passive"))
    )
    (net (code "91") (name "LTDC_G2") (class "Default")
      (node (ref "IC4") (pin "52") (pinfunction "PA6_52") (pintype "bidirectional"))
      (node (ref "LCD1") (pin "15") (pinfunction "G2_15") (pintype "input"))
    )
    (net (code "92") (name "LTDC_G3") (class "Default")
      (node (ref "IC4") (pin "153") (pinfunction "PG10_153") (pintype "bidirectional"))
      (node (ref "LCD1") (pin "16") (pinfunction "G3_16") (pintype "input"))
    )
    (net (code "93") (name "LTDC_G4") (class "Default")
      (node (ref "IC4") (pin "45") (pinfunction "PH4_45") (pintype "bidirectional"))
      (node (ref "LCD1") (pin "17") (pinfunction "G4_17") (pintype "input"))
    )
    (net (code "94") (name "LTDC_G5") (class "Default")
      (node (ref "IC4") (pin "132") (pinfunction "PI0_132") (pintype "bidirectional"))
      (node (ref "LCD1") (pin "18") (pinfunction "G5_18") (pintype "input"))
    )
    (net (code "95") (name "LTDC_G6") (class "Default")
      (node (ref "IC4") (pin "13") (pinfunction "PI11_13") (pintype "bidirectional"))
      (node (ref "LCD1") (pin "19") (pinfunction "G6_19") (pintype "input"))
    )
    (net (code "96") (name "LTDC_G7") (class "Default")
      (node (ref "IC4") (pin "145") (pinfunction "PD3_145") (pintype "bidirectional"))
      (node (ref "LCD1") (pin "20") (pinfunction "G7_20") (pintype "input"))
    )
    (net (code "97") (name "LTDC_HSYNC") (class "Default")
      (node (ref "IC4") (pin "12") (pinfunction "PI10_12") (pintype "bidirectional"))
      (node (ref "LCD1") (pin "32") (pinfunction "HSYNC_32") (pintype "input"))
    )
    (net (code "98") (name "LTDC_R2") (class "Default")
      (node (ref "IC4") (pin "139") (pinfunction "PC10_139") (pintype "bidirectional"))
      (node (ref "LCD1") (pin "7") (pinfunction "R2_7") (pintype "input"))
    )
    (net (code "99") (name "LTDC_R3") (class "Default")
      (node (ref "IC4") (pin "56") (pinfunction "PB0_56") (pintype "bidirectional"))
      (node (ref "LCD1") (pin "8") (pinfunction "R3_8") (pintype "input"))
    )
    (net (code "100") (name "LTDC_R4") (class "Default")
      (node (ref "IC4") (pin "51") (pinfunction "PA5_51") (pintype "bidirectional"))
      (node (ref "LCD1") (pin "9") (pinfunction "R4_9") (pintype "input"))
    )
    (net (code "101") (name "LTDC_R5") (class "Default")
      (node (ref "IC4") (pin "32") (pinfunction "PC0_32") (pintype "bidirectional"))
      (node (ref "LCD1") (pin "10") (pinfunction "R5_10") (pintype "input"))
    )
    (net (code "102") (name "LTDC_R6") (class "Default")
      (node (ref "IC4") (pin "57") (pinfunction "PB1_57") (pintype "bidirectional"))
      (node (ref "LCD1") (pin "11") (pinfunction "R6_11") (pintype "input"))
    )
    (net (code "103") (name "LTDC_R7") (class "Default")
      (node (ref "IC4") (pin "114") (pinfunction "PG6_114") (pintype "bidirectional"))
      (node (ref "LCD1") (pin "12") (pinfunction "R7_12") (pintype "input"))
    )
    (net (code "104") (name "LTDC_VSYNC") (class "Default")
      (node (ref "IC4") (pin "11") (pinfunction "PI9_11") (pintype "bidirectional"))
      (node (ref "LCD1") (pin "33") (pinfunction "VSYNC_33") (pintype "input"))
    )
    (net (code "105") (name "MCLK_25") (class "Default")
      (node (ref "IC4") (pin "122") (pinfunction "PC9_122") (pintype "bidirectional"))
      (node (ref "RN1") (pin "1") (pinfunction "1_1") (pintype "passive"))
    )
    (net (code "106") (name "Net-(B1-+-Pad1)") (class "Default")
      (node (ref "B1") (pin "1") (pinfunction "+_1") (pintype "passive"))
      (node (ref "B1") (pin "3") (pinfunction "+_3") (pintype "passive"))
      (node (ref "JP5") (pin "1") (pinfunction "1_1") (pintype "passive"))
      (node (ref "JP6") (pin "NC") (pinfunction "NC_NC") (pintype "passive"))
    )
    (net (code "107") (name "Net-(C54-Pad1)") (class "Default")
      (node (ref "C54") (pin "1") (pinfunction "1_1") (pintype "passive"))
      (node (ref "R34") (pin "2") (pinfunction "2_2") (pintype "passive"))
    )
    (net (code "108") (name "Net-(C55-Pad1)") (class "Default")
      (node (ref "C55") (pin "1") (pinfunction "1_1") (pintype "passive"))
      (node (ref "R35") (pin "2") (pinfunction "2_2") (pintype "passive"))
    )
    (net (code "109") (name "Net-(C61-Pad1)") (class "Default")
      (node (ref "C61") (pin "1") (pinfunction "1_1") (pintype "passive"))
      (node (ref "R40") (pin "1") (pinfunction "1_1") (pintype "passive"))
      (node (ref "R41") (pin "2") (pinfunction "2_2") (pintype "passive"))
    )
    (net (code "110") (name "Net-(C63-Pad1)") (class "Default")
      (node (ref "C63") (pin "1") (pinfunction "1_1") (pintype "passive"))
      (node (ref "R44") (pin "1") (pinfunction "1_1") (pintype "passive"))
      (node (ref "R49") (pin "2") (pinfunction "2_2") (pintype "passive"))
    )
    (net (code "111") (name "Net-(F1-P$1)") (class "Default")
      (node (ref "F1") (pin "1") (pinfunction "P$1_1") (pintype "bidirectional"))
      (node (ref "X3") (pin "4") (pinfunction "1_4") (pintype "passive"))
    )
    (net (code "112") (name "Net-(F1-P$2)") (class "Default")
      (node (ref "F1") (pin "2") (pinfunction "P$2_2") (pintype "bidirectional"))
      (node (ref "IC1") (pin "4") (pinfunction "IO3_4") (pintype "bidirectional"))
      (node (ref "IC3") (pin "7") (pinfunction "OUT1_7") (pintype "output"))
      (node (ref "ZD1") (pin "C") (pinfunction "C_C") (pintype "passive"))
    )
    (net (code "113") (name "Net-(F2-P$1)") (class "Default")
      (node (ref "F2") (pin "1") (pinfunction "P$1_1") (pintype "bidirectional"))
      (node (ref "X3") (pin "5") (pinfunction "1_5") (pintype "passive"))
    )
    (net (code "114") (name "Net-(F2-P$2)") (class "Default")
      (node (ref "F2") (pin "2") (pinfunction "P$2_2") (pintype "bidirectional"))
      (node (ref "IC1") (pin "5") (pinfunction "IO4_5") (pintype "bidirectional"))
      (node (ref "IC3") (pin "5") (pinfunction "OUT2_5") (pintype "output"))
      (node (ref "ZD2") (pin "C") (pinfunction "C_C") (pintype "passive"))
    )
    (net (code "115") (name "Net-(IC1-IO1)") (class "Default")
      (node (ref "IC1") (pin "1") (pinfunction "IO1_1") (pintype "bidirectional"))
      (node (ref "IC2") (pin "1") (pinfunction "I_1") (pintype "input"))
      (node (ref "R3") (pin "2") (pinfunction "2_2") (pintype "passive"))
    )
    (net (code "116") (name "Net-(IC1-IO2)") (class "Default")
      (node (ref "IC1") (pin "2") (pinfunction "IO2_2") (pintype "bidirectional"))
      (node (ref "IC2") (pin "3") (pinfunction "I_3") (pintype "input"))
      (node (ref "R7") (pin "2") (pinfunction "2_2") (pintype "passive"))
    )
    (net (code "117") (name "Net-(IC2A-O)") (class "Default")
      (node (ref "IC2") (pin "6") (pinfunction "O_6") (pintype "output"))
      (node (ref "R4") (pin "1") (pinfunction "1_1") (pintype "passive"))
    )
    (net (code "118") (name "Net-(IC2B-O)") (class "Default")
      (node (ref "IC2") (pin "4") (pinfunction "O_4") (pintype "output"))
      (node (ref "R8") (pin "1") (pinfunction "1_1") (pintype "passive"))
    )
    (net (code "119") (name "Net-(IC4D-VCAPDSI)") (class "Default")
      (node (ref "IC4") (pin "100") (pinfunction "VCAPDSI_100") (pintype "power_in"))
      (node (ref "IC4") (pin "106") (pinfunction "VDD12DSI_106") (pintype "power_in"))
    )
    (net (code "120") (name "Net-(IC10-SW)") (class "Default")
      (node (ref "D2") (pin "A") (pinfunction "A_A") (pintype "passive"))
      (node (ref "IC10") (pin "1") (pinfunction "SW_1") (pintype "output"))
      (node (ref "L1") (pin "2") (pinfunction "2_2") (pintype "passive"))
    )
    (net (code "121") (name "Net-(IC10-VIN)") (class "Default")
      (node (ref "IC10") (pin "5") (pinfunction "VIN_5") (pintype "input"))
      (node (ref "R24") (pin "2") (pinfunction "2_2") (pintype "passive"))
    )
    (net (code "122") (name "Net-(IC12-BYPASS)") (class "Default")
      (node (ref "C59") (pin "2") (pinfunction "2_2") (pintype "passive"))
      (node (ref "IC12") (pin "2") (pinfunction "BYPASS_2") (pintype "input"))
    )
    (net (code "123") (name "Net-(IC12-IN+)") (class "Default")
      (node (ref "IC12") (pin "3") (pinfunction "IN+_3") (pintype "input"))
      (node (ref "R32") (pin "2") (pinfunction "2_2") (pintype "passive"))
      (node (ref "R34") (pin "1") (pinfunction "1_1") (pintype "passive"))
    )
    (net (code "124") (name "Net-(IC12-IN-)") (class "Default")
      (node (ref "IC12") (pin "4") (pinfunction "IN-_4") (pintype "input"))
      (node (ref "R35") (pin "1") (pinfunction "1_1") (pintype "passive"))
      (node (ref "R37") (pin "2") (pinfunction "2_2") (pintype "passive"))
    )
    (net (code "125") (name "Net-(IC12-VDD)") (class "Default")
      (node (ref "C53") (pin "2") (pinfunction "2_2") (pintype "passive"))
      (node (ref "IC12") (pin "6") (pinfunction "VDD_6") (pintype "power_in"))
      (node (ref "JP10") (pin "COM") (pinfunction "COM_COM") (pintype "passive"))
    )
    (net (code "126") (name "Net-(IC12-VO+)") (class "Default")
      (node (ref "IC12") (pin "5") (pinfunction "VO+_5") (pintype "output"))
      (node (ref "R38") (pin "1") (pinfunction "1_1") (pintype "passive"))
      (node (ref "SP1") (pin "+") (pinfunction "+_+") (pintype "passive"))
    )
    (net (code "127") (name "Net-(IC12-VO-)") (class "Default")
      (node (ref "IC12") (pin "8") (pinfunction "VO-_8") (pintype "output"))
      (node (ref "R33") (pin "1") (pinfunction "1_1") (pintype "passive"))
      (node (ref "SP1") (pin "-") (pinfunction "-_-") (pintype "passive"))
    )
    (net (code "128") (name "Net-(IC12-~{SHDN})") (class "Default")
      (node (ref "IC12") (pin "1") (pinfunction "~{SHDN}_1") (pintype "input"))
      (node (ref "R36") (pin "1") (pinfunction "1_1") (pintype "passive"))
    )
    (net (code "129") (name "Net-(IC15-IO1)") (class "Default")
      (node (ref "IC15") (pin "1") (pinfunction "IO1_1") (pintype "bidirectional"))
      (node (ref "IC16") (pin "17") (pinfunction "TD+_17") (pintype "bidirectional"))
      (node (ref "R40") (pin "2") (pinfunction "2_2") (pintype "passive"))
      (node (ref "X5") (pin "1") (pinfunction "TD+_1") (pintype "input"))
    )
    (net (code "130") (name "Net-(IC15-IO2)") (class "Default")
      (node (ref "IC15") (pin "2") (pinfunction "IO2_2") (pintype "bidirectional"))
      (node (ref "IC16") (pin "16") (pinfunction "TD-_16") (pintype "bidirectional"))
      (node (ref "R41") (pin "1") (pinfunction "1_1") (pintype "passive"))
      (node (ref "X5") (pin "2") (pinfunction "TD-_2") (pintype "input"))
    )
    (net (code "131") (name "Net-(IC15-IO3)") (class "Default")
      (node (ref "IC15") (pin "4") (pinfunction "IO3_4") (pintype "bidirectional"))
      (node (ref "IC16") (pin "14") (pinfunction "RD+_14") (pintype "bidirectional"))
      (node (ref "R44") (pin "2") (pinfunction "2_2") (pintype "passive"))
      (node (ref "X5") (pin "7") (pinfunction "RD+_7") (pintype "input"))
    )
    (net (code "132") (name "Net-(IC15-IO4)") (class "Default")
      (node (ref "IC15") (pin "5") (pinfunction "IO4_5") (pintype "bidirectional"))
      (node (ref "IC16") (pin "13") (pinfunction "RD-_13") (pintype "bidirectional"))
      (node (ref "R49") (pin "1") (pinfunction "1_1") (pintype "passive"))
      (node (ref "X5") (pin "8") (pinfunction "RD-_8") (pintype "input"))
    )
    (net (code "133") (name "Net-(IC16-CRS{slash}CRS_DV{slash}LED_CFG)") (class "Default")
      (node (ref "IC16") (pin "40") (pinfunction "CRS/CRS_DV/LED_CFG_40") (pintype "output"))
      (node (ref "RN1") (pin "5") (pinfunction "2_5") (pintype "passive"))
    )
    (net (code "134") (name "Net-(IC16-MDIX_EN(RX_ER))") (class "Default")
      (node (ref "IC16") (pin "41") (pinfunction "MDIX_EN(RX_ER)_41") (pintype "output"))
      (node (ref "RN2") (pin "8") (pinfunction "2_8") (pintype "passive"))
    )
    (net (code "135") (name "Net-(IC16-MII_MODE(RX_DV))") (class "Default")
      (node (ref "IC16") (pin "39") (pinfunction "MII_MODE(RX_DV)_39") (pintype "output"))
      (node (ref "JP13") (pin "2") (pinfunction "2_2") (pintype "passive"))
      (node (ref "RN1") (pin "6") (pinfunction "2_6") (pintype "passive"))
    )
    (net (code "136") (name "Net-(IC16-PFBIN1)") (class "Default")
      (node (ref "C65") (pin "1") (pinfunction "1_1") (pintype "passive"))
      (node (ref "C66") (pin "1") (pinfunction "1_1") (pintype "passive"))
      (node (ref "C67") (pin "+") (pinfunction "+_+") (pintype "passive"))
      (node (ref "C68") (pin "1") (pinfunction "1_1") (pintype "passive"))
      (node (ref "IC16") (pin "18") (pinfunction "PFBIN1_18") (pintype "input"))
      (node (ref "IC16") (pin "23") (pinfunction "PFBOUT_23") (pintype "output"))
      (node (ref "IC16") (pin "37") (pinfunction "PFBIN2_37") (pintype "input"))
    )
    (net (code "137") (name "Net-(IC16-PHYAD0(COL))") (class "Default")
      (node (ref "IC16") (pin "42") (pinfunction "PHYAD0(COL)_42") (pintype "output"))
      (node (ref "RN2") (pin "7") (pinfunction "2_7") (pintype "passive"))
    )
    (net (code "138") (name "Net-(IC16-PHYAD1(RXD1_0))") (class "Default")
      (node (ref "IC16") (pin "43") (pinfunction "PHYAD1(RXD1_0)_43") (pintype "output"))
      (node (ref "RN2") (pin "6") (pinfunction "2_6") (pintype "passive"))
    )
    (net (code "139") (name "Net-(IC16-PHYAD2(RXD1_1))") (class "Default")
      (node (ref "IC16") (pin "44") (pinfunction "PHYAD2(RXD1_1)_44") (pintype "output"))
      (node (ref "RN2") (pin "5") (pinfunction "2_5") (pintype "passive"))
    )
    (net (code "140") (name "Net-(IC16-PHYAD3(RXD1_2))") (class "Default")
      (node (ref "IC16") (pin "45") (pinfunction "PHYAD3(RXD1_2)_45") (pintype "output"))
      (node (ref "RN3") (pin "8") (pinfunction "2_8") (pintype "passive"))
    )
    (net (code "141") (name "Net-(IC16-PHYAD4(RXD1_3))") (class "Default")
      (node (ref "IC16") (pin "46") (pinfunction "PHYAD4(RXD1_3)_46") (pintype "output"))
      (node (ref "RN3") (pin "7") (pinfunction "2_7") (pintype "passive"))
    )
    (net (code "142") (name "Net-(IC16-PWR_DOWN{slash}INT)") (class "Default")
      (node (ref "IC16") (pin "7") (pinfunction "PWR_DOWN/INT_7") (pintype "input"))
      (node (ref "JP15") (pin "2") (pinfunction "2_2") (pintype "passive"))
    )
    (net (code "143") (name "Net-(IC16-RBIAS)") (class "Default")
      (node (ref "IC16") (pin "24") (pinfunction "RBIAS_24") (pintype "input"))
      (node (ref "R55") (pin "2") (pinfunction "2_2") (pintype "passive"))
    )
    (net (code "144") (name "Net-(IC16-RESERVED-20)") (class "Default")
      (node (ref "IC16") (pin "20") (pinfunction "RESERVED-20_20") (pintype "bidirectional"))
      (node (ref "R54") (pin "2") (pinfunction "2_2") (pintype "passive"))
    )
    (net (code "145") (name "Net-(IC16-RESERVED-21)") (class "Default")
      (node (ref "IC16") (pin "21") (pinfunction "RESERVED-21_21") (pintype "bidirectional"))
      (node (ref "R53") (pin "2") (pinfunction "2_2") (pintype "passive"))
    )
    (net (code "146") (name "Net-(IC16-RX_CLK)") (class "Default")
      (node (ref "IC16") (pin "38") (pinfunction "RX_CLK_38") (pintype "output"))
      (node (ref "RN1") (pin "7") (pinfunction "2_7") (pintype "passive"))
    )
    (net (code "147") (name "Net-(IC16-TXD_0)") (class "Default")
      (node (ref "IC16") (pin "3") (pinfunction "TXD_0_3") (pintype "input"))
      (node (ref "RN4") (pin "8") (pinfunction "2_8") (pintype "passive"))
    )
    (net (code "148") (name "Net-(IC16-TXD_1)") (class "Default")
      (node (ref "IC16") (pin "4") (pinfunction "TXD_1_4") (pintype "input"))
      (node (ref "RN4") (pin "7") (pinfunction "2_7") (pintype "passive"))
    )
    (net (code "149") (name "Net-(IC16-TXD_2)") (class "Default")
      (node (ref "IC16") (pin "5") (pinfunction "TXD_2_5") (pintype "input"))
      (node (ref "RN4") (pin "6") (pinfunction "2_6") (pintype "passive"))
    )
    (net (code "150") (name "Net-(IC16-TXD_3{slash}SNI_MODE)") (class "Default")
      (node (ref "IC16") (pin "6") (pinfunction "TXD_3/SNI_MODE_6") (pintype "input"))
      (node (ref "RN4") (pin "5") (pinfunction "2_5") (pintype "passive"))
    )
    (net (code "151") (name "Net-(IC16-TX_CLK)") (class "Default")
      (node (ref "IC16") (pin "1") (pinfunction "TX_CLK_1") (pintype "output"))
      (node (ref "RN3") (pin "6") (pinfunction "2_6") (pintype "passive"))
    )
    (net (code "152") (name "Net-(IC16-TX_EN)") (class "Default")
      (node (ref "IC16") (pin "2") (pinfunction "TX_EN_2") (pintype "input"))
      (node (ref "RN3") (pin "5") (pinfunction "2_5") (pintype "passive"))
    )
    (net (code "153") (name "Net-(IC16-X1)") (class "Default")
      (node (ref "IC16") (pin "34") (pinfunction "X1_34") (pintype "input"))
      (node (ref "RN1") (pin "8") (pinfunction "2_8") (pintype "passive"))
    )
    (net (code "154") (name "Net-(JP11-Pad2)") (class "Default")
      (node (ref "JP11") (pin "2") (pinfunction "2_2") (pintype "passive"))
      (node (ref "R45") (pin "2") (pinfunction "2_2") (pintype "passive"))
    )
    (net (code "155") (name "Net-(JP12-Pad1)") (class "Default")
      (node (ref "JP12") (pin "1") (pinfunction "1_1") (pintype "passive"))
      (node (ref "JP14") (pin "1") (pinfunction "1_1") (pintype "passive"))
      (node (ref "RN2") (pin "1") (pinfunction "1_1") (pintype "passive"))
    )
    (net (code "156") (name "Net-(JP12-Pad2)") (class "Default")
      (node (ref "JP12") (pin "2") (pinfunction "2_2") (pintype "passive"))
      (node (ref "R42") (pin "2") (pinfunction "2_2") (pintype "passive"))
    )
    (net (code "157") (name "Net-(JP13-Pad1)") (class "Default")
      (node (ref "JP13") (pin "1") (pinfunction "1_1") (pintype "passive"))
      (node (ref "R47") (pin "2") (pinfunction "2_2") (pintype "passive"))
    )
    (net (code "158") (name "Net-(JP15-Pad1)") (class "Default")
      (node (ref "JP15") (pin "1") (pinfunction "1_1") (pintype "passive"))
      (node (ref "R56") (pin "2") (pinfunction "2_2") (pintype "passive"))
    )
    (net (code "159") (name "Net-(LCD1-B0)") (class "Default")
      (node (ref "JP8") (pin "COM") (pinfunction "COM_COM") (pintype "passive"))
      (node (ref "LCD1") (pin "13") (pinfunction "G0_13") (pintype "input"))
      (node (ref "LCD1") (pin "14") (pinfunction "G1_14") (pintype "input"))
      (node (ref "LCD1") (pin "21") (pinfunction "B0_21") (pintype "input"))
      (node (ref "LCD1") (pin "22") (pinfunction "B1_22") (pintype "input"))
      (node (ref "LCD1") (pin "5") (pinfunction "R0_5") (pintype "input"))
      (node (ref "LCD1") (pin "6") (pinfunction "R1_6") (pintype "input"))
    )
    (net (code "160") (name "Net-(LCD1-RESET)") (class "Default")
      (node (ref "JP9") (pin "COM") (pinfunction "COM_COM") (pintype "passive"))
      (node (ref "LCD1") (pin "36") (pinfunction "RESET_36") (pintype "input"))
    )
    (net (code "161") (name "Net-(Q1-PadB)") (class "Default")
      (node (ref "Q1") (pin "B") (pinfunction "B_B") (pintype "passive"))
      (node (ref "R28") (pin "2") (pinfunction "2_2") (pintype "passive"))
    )
    (net (code "162") (name "Net-(Q1-PadC)") (class "Default")
      (node (ref "Q1") (pin "C") (pinfunction "C_C") (pintype "passive"))
      (node (ref "R25") (pin "1") (pinfunction "1_1") (pintype "passive"))
    )
    (net (code "163") (name "Net-(R1-Pad2)") (class "Default")
      (node (ref "R1") (pin "2") (pinfunction "2_2") (pintype "passive"))
      (node (ref "R5") (pin "2") (pinfunction "2_2") (pintype "passive"))
      (node (ref "SW2") (pin "A") (pinfunction "A_A") (pintype "passive"))
    )
    (net (code "164") (name "Net-(R2-Pad1)") (class "Default")
      (node (ref "R2") (pin "1") (pinfunction "1_1") (pintype "passive"))
      (node (ref "X3") (pin "1") (pinfunction "1_1") (pintype "passive"))
    )
    (net (code "165") (name "Net-(R2-Pad2)") (class "Default")
      (node (ref "R2") (pin "2") (pinfunction "2_2") (pintype "passive"))
      (node (ref "R3") (pin "1") (pinfunction "1_1") (pintype "passive"))
    )
    (net (code "166") (name "Net-(R6-Pad2)") (class "Default")
      (node (ref "R6") (pin "2") (pinfunction "2_2") (pintype "passive"))
      (node (ref "R7") (pin "1") (pinfunction "1_1") (pintype "passive"))
    )
    (net (code "167") (name "Net-(R10-Pad2)") (class "Default")
      (node (ref "R10") (pin "2") (pinfunction "2_2") (pintype "passive"))
      (node (ref "R9") (pin "2") (pinfunction "2_2") (pintype "passive"))
      (node (ref "SW2") (pin "B") (pinfunction "B_B") (pintype "passive"))
    )
    (net (code "168") (name "Net-(R25-Pad2)") (class "Default")
      (node (ref "R25") (pin "2") (pinfunction "2_2") (pintype "passive"))
      (node (ref "VBUS") (pin "C") (pinfunction "C_C") (pintype "passive"))
    )
    (net (code "169") (name "Net-(R32-Pad1)") (class "Default")
      (node (ref "R32") (pin "1") (pinfunction "1_1") (pintype "passive"))
      (node (ref "R33") (pin "2") (pinfunction "2_2") (pintype "passive"))
    )
    (net (code "170") (name "Net-(R37-Pad1)") (class "Default")
      (node (ref "R37") (pin "1") (pinfunction "1_1") (pintype "passive"))
      (node (ref "R38") (pin "2") (pinfunction "2_2") (pintype "passive"))
    )
    (net (code "171") (name "Net-(R46-Pad2)") (class "Default")
      (node (ref "R46") (pin "2") (pinfunction "2_2") (pintype "passive"))
      (node (ref "SPEED") (pin "A") (pinfunction "A_A") (pintype "passive"))
    )
    (net (code "172") (name "Net-(X2E-1)") (class "Default")
      (node (ref "JP2") (pin "2") (pinfunction "2_2") (pintype "passive"))
      (node (ref "X2") (pin "13") (pinfunction "1_13") (pintype "passive"))
    )
    (net (code "173") (name "Net-(X2F-1)") (class "Default")
      (node (ref "JP3") (pin "1") (pinfunction "1_1") (pintype "passive"))
      (node (ref "X2") (pin "14") (pinfunction "1_14") (pintype "passive"))
    )
    (net (code "174") (name "Net-(X3B-1)") (class "Default")
      (node (ref "R6") (pin "1") (pinfunction "1_1") (pintype "passive"))
      (node (ref "X3") (pin "2") (pinfunction "1_2") (pintype "passive"))
    )
    (net (code "175") (name "Net-(X4A-S)") (class "Default")
      (node (ref "JP7") (pin "2") (pinfunction "2_2") (pintype "passive"))
      (node (ref "R18") (pin "2") (pinfunction "2_2") (pintype "passive"))
      (node (ref "X4") (pin "1") (pinfunction "S_1") (pintype "passive"))
    )
    (net (code "176") (name "Net-(X5-GREEN-C)") (class "Default")
      (node (ref "R52") (pin "1") (pinfunction "1_1") (pintype "passive"))
      (node (ref "X5") (pin "10") (pinfunction "GREEN-C_10") (pintype "passive"))
    )
    (net (code "177") (name "Net-(X5-YELLOW-C)") (class "Default")
      (node (ref "R51") (pin "1") (pinfunction "1_1") (pintype "passive"))
      (node (ref "X5") (pin "11") (pinfunction "YELLOW-C_11") (pintype "passive"))
    )
    (net (code "178") (name "OE_SYNC") (class "Default")
      (node (ref "IC4") (pin "94") (pinfunction "PD13_94") (pintype "bidirectional"))
      (node (ref "X1") (pin "10") (pinfunction "1_10") (pintype "passive"))
    )
    (net (code "179") (name "PE") (class "Default")
      (node (ref "C1") (pin "1") (pinfunction "1_1") (pintype "passive"))
      (node (ref "C51") (pin "1") (pinfunction "1_1") (pintype "passive"))
      (node (ref "J2") (pin "SH1") (pinfunction "SH1_SH1") (pintype "bidirectional"))
      (node (ref "J2") (pin "SH1.1") (pinfunction "SH1_SH1.1") (pintype "bidirectional"))
      (node (ref "J2") (pin "SH2") (pinfunction "SH2_SH2") (pintype "bidirectional"))
      (node (ref "J2") (pin "SH2.2") (pinfunction "SH2_SH2.2") (pintype "bidirectional"))
      (node (ref "JP1") (pin "2") (pinfunction "2_2") (pintype "passive"))
      (node (ref "X2") (pin "1") (pinfunction "1_1") (pintype "passive"))
      (node (ref "X5") (pin "SH") (pinfunction "SH_SH") (pintype "passive"))
      (node (ref "X5") (pin "SH2") (pinfunction "SH_SH2") (pintype "passive"))
    )
    (net (code "180") (name "PWR_DIRECT") (class "Default")
      (node (ref "IC4") (pin "110") (pinfunction "PG2_110") (pintype "bidirectional"))
      (node (ref "X2") (pin "12") (pinfunction "1_12") (pintype "passive"))
    )
    (net (code "181") (name "PWR_SSTART") (class "Default")
      (node (ref "IC4") (pin "111") (pinfunction "PG3_111") (pintype "bidirectional"))
      (node (ref "X2") (pin "11") (pinfunction "1_11") (pintype "passive"))
    )
    (net (code "182") (name "RCC_OSC32_IN") (class "Default")
      (node (ref "C10") (pin "1") (pinfunction "1_1") (pintype "passive"))
      (node (ref "IC4") (pin "9") (pinfunction "PC14_9") (pintype "bidirectional"))
      (node (ref "Y2") (pin "1") (pinfunction "1_1") (pintype "passive"))
    )
    (net (code "183") (name "RCC_OSC32_OUT") (class "Default")
      (node (ref "C12") (pin "1") (pinfunction "1_1") (pintype "passive"))
      (node (ref "IC4") (pin "10") (pinfunction "PC15_10") (pintype "bidirectional"))
      (node (ref "Y2") (pin "4") (pinfunction "2_4") (pintype "passive"))
    )
    (net (code "184") (name "RCC_OSC_IN") (class "Default")
      (node (ref "C9") (pin "2") (pinfunction "2_2") (pintype "passive"))
      (node (ref "IC4") (pin "29") (pinfunction "PH0_29") (pintype "bidirectional"))
      (node (ref "Y1") (pin "2") (pinfunction "2_2") (pintype "passive"))
    )
    (net (code "185") (name "RCC_OSC_OUT") (class "Default")
      (node (ref "C11") (pin "2") (pinfunction "2_2") (pintype "passive"))
      (node (ref "IC4") (pin "30") (pinfunction "PH1_30") (pintype "bidirectional"))
      (node (ref "Y1") (pin "1") (pinfunction "1_1") (pintype "passive"))
    )
    (net (code "186") (name "SDMMC1_CK") (class "Default")
      (node (ref "IC4") (pin "141") (pinfunction "PC12_141") (pintype "bidirectional"))
      (node (ref "J1") (pin "5") (pinfunction "CLK_5") (pintype "passive"))
    )
    (net (code "187") (name "SDMMC1_CMD") (class "Default")
      (node (ref "IC4") (pin "144") (pinfunction "PD2_144") (pintype "bidirectional"))
      (node (ref "J1") (pin "3") (pinfunction "CMD_3") (pintype "passive"))
      (node (ref "R22") (pin "2") (pinfunction "2_2") (pintype "passive"))
    )
    (net (code "188") (name "SDMMC1_D0") (class "Default")
      (node (ref "IC4") (pin "121") (pinfunction "PC8_121") (pintype "bidirectional"))
      (node (ref "J1") (pin "7") (pinfunction "DAT0_7") (pintype "passive"))
      (node (ref "R21") (pin "2") (pinfunction "2_2") (pintype "passive"))
    )
    (net (code "189") (name "SD_DETECT") (class "Default")
      (node (ref "IC4") (pin "140") (pinfunction "PC11_140") (pintype "bidirectional"))
      (node (ref "J1") (pin "SW1") (pinfunction "SW1_SW1") (pintype "passive"))
    )
    (net (code "190") (name "SPI2_CLK") (class "Default")
      (node (ref "IC4") (pin "133") (pinfunction "PI1_133") (pintype "bidirectional"))
      (node (ref "X1") (pin "32") (pinfunction "1_32") (pintype "passive"))
    )
    (net (code "191") (name "SPI2_CSA") (class "Default")
      (node (ref "IC4") (pin "93") (pinfunction "PD12_93") (pintype "bidirectional"))
      (node (ref "X1") (pin "28") (pinfunction "1_28") (pintype "passive"))
    )
    (net (code "192") (name "SPI2_CSB") (class "Default")
      (node (ref "IC4") (pin "92") (pinfunction "PD11_92") (pintype "bidirectional"))
      (node (ref "X1") (pin "27") (pinfunction "1_27") (pintype "passive"))
    )
    (net (code "193") (name "SPI2_IRQ") (class "Default")
      (node (ref "IC4") (pin "123") (pinfunction "PA8_123") (pintype "bidirectional"))
      (node (ref "X1") (pin "25") (pinfunction "1_25") (pintype "passive"))
    )
    (net (code "194") (name "SPI2_MISO") (class "Default")
      (node (ref "IC4") (pin "87") (pinfunction "PB14_87") (pintype "bidirectional"))
      (node (ref "X1") (pin "31") (pinfunction "1_31") (pintype "passive"))
    )
    (net (code "195") (name "SPI2_MOSI") (class "Default")
      (node (ref "IC4") (pin "134") (pinfunction "PI3_134") (pintype "bidirectional"))
      (node (ref "X1") (pin "33") (pinfunction "1_33") (pintype "passive"))
    )
    (net (code "196") (name "SPI4_CLK") (class "Default")
      (node (ref "IC4") (pin "1") (pinfunction "PE2_1") (pintype "bidirectional"))
      (node (ref "X1") (pin "23") (pinfunction "1_23") (pintype "passive"))
    )
    (net (code "197") (name "SPI4_CSA") (class "Default")
      (node (ref "IC4") (pin "2") (pinfunction "PE3_2") (pintype "bidirectional"))
      (node (ref "X1") (pin "22") (pinfunction "1_22") (pintype "passive"))
    )
    (net (code "198") (name "SPI4_CSB") (class "Default")
      (node (ref "IC4") (pin "3") (pinfunction "PE4_3") (pintype "bidirectional"))
      (node (ref "X1") (pin "21") (pinfunction "1_21") (pintype "passive"))
    )
    (net (code "199") (name "SPI4_IRQ") (class "Default")
      (node (ref "IC4") (pin "168") (pinfunction "PB9_168") (pintype "bidirectional"))
      (node (ref "X1") (pin "19") (pinfunction "1_19") (pintype "passive"))
    )
    (net (code "200") (name "SPI4_MISO") (class "Default")
      (node (ref "IC4") (pin "4") (pinfunction "PE5_4") (pintype "bidirectional"))
      (node (ref "X1") (pin "24") (pinfunction "1_24") (pintype "passive"))
    )
    (net (code "201") (name "SPI4_MOSI") (class "Default")
      (node (ref "IC4") (pin "5") (pinfunction "PE6_5") (pintype "bidirectional"))
      (node (ref "X1") (pin "26") (pinfunction "1_26") (pintype "passive"))
    )
    (net (code "202") (name "SPI5_CLK") (class "Default")
      (node (ref "IC4") (pin "25") (pinfunction "PF7_25") (pintype "bidirectional"))
      (node (ref "X1") (pin "17") (pinfunction "1_17") (pintype "passive"))
    )
    (net (code "203") (name "SPI5_CSA") (class "Default")
      (node (ref "IC4") (pin "157") (pinfunction "PG14_157") (pintype "bidirectional"))
      (node (ref "X1") (pin "11") (pinfunction "1_11") (pintype "passive"))
    )
    (net (code "204") (name "SPI5_CSB") (class "Default")
      (node (ref "IC4") (pin "156") (pinfunction "PG13_156") (pintype "bidirectional"))
      (node (ref "X1") (pin "13") (pinfunction "1_13") (pintype "passive"))
    )
    (net (code "205") (name "SPI5_IRQ") (class "Default")
      (node (ref "IC4") (pin "138") (pinfunction "PA15_138") (pintype "bidirectional"))
      (node (ref "X1") (pin "9") (pinfunction "1_9") (pintype "passive"))
    )
    (net (code "206") (name "SPI5_MISO") (class "Default")
      (node (ref "IC4") (pin "26") (pinfunction "PF8_26") (pintype "bidirectional"))
      (node (ref "X1") (pin "18") (pinfunction "1_18") (pintype "passive"))
    )
    (net (code "207") (name "SPI5_MOSI") (class "Default")
      (node (ref "IC4") (pin "27") (pinfunction "PF9_27") (pintype "bidirectional"))
      (node (ref "X1") (pin "20") (pinfunction "1_20") (pintype "passive"))
    )
    (net (code "208") (name "SYS_JTCK-SWCLK") (class "Default")
      (node (ref "IC4") (pin "137") (pinfunction "PA14_137") (pintype "bidirectional"))
      (node (ref "R20") (pin "1") (pinfunction "1_1") (pintype "passive"))
    )
    (net (code "209") (name "SYS_JTDO-SWO") (class "Default")
      (node (ref "IC4") (pin "161") (pinfunction "PB3_161") (pintype "bidirectional"))
      (node (ref "IC6") (pin "5") (pinfunction "IO4_5") (pintype "bidirectional"))
      (node (ref "X4") (pin "6") (pinfunction "S_6") (pintype "passive"))
    )
    (net (code "210") (name "SYS_JTMS-SWDIO") (class "Default")
      (node (ref "IC4") (pin "128") (pinfunction "PA13_128") (pintype "bidirectional"))
      (node (ref "R19") (pin "1") (pinfunction "1_1") (pintype "passive"))
    )
    (net (code "211") (name "TCK") (class "Default")
      (node (ref "IC6") (pin "1") (pinfunction "IO1_1") (pintype "bidirectional"))
      (node (ref "R20") (pin "2") (pinfunction "2_2") (pintype "passive"))
      (node (ref "X4") (pin "2") (pinfunction "S_2") (pintype "passive"))
    )
    (net (code "212") (name "TFT_BRIGHTNESS") (class "Default")
      (node (ref "IC10") (pin "4") (pinfunction "CTRL_4") (pintype "input"))
      (node (ref "IC4") (pin "88") (pinfunction "PB15_88") (pintype "bidirectional"))
    )
    (net (code "213") (name "TMS") (class "Default")
      (node (ref "IC6") (pin "2") (pinfunction "IO2_2") (pintype "bidirectional"))
      (node (ref "R19") (pin "2") (pinfunction "2_2") (pintype "passive"))
      (node (ref "X4") (pin "4") (pinfunction "S_4") (pintype "passive"))
    )
    (net (code "214") (name "UART_RX{slash}DIN1") (class "Default")
      (node (ref "IC4") (pin "24") (pinfunction "PF6_24") (pintype "bidirectional"))
      (node (ref "R4") (pin "2") (pinfunction "2_2") (pintype "passive"))
      (node (ref "X1") (pin "3") (pinfunction "1_3") (pintype "passive"))
    )
    (net (code "215") (name "UART_TX{slash}DOUT1") (class "Default")
      (node (ref "IC3") (pin "2") (pinfunction "IN1_2") (pintype "input"))
      (node (ref "IC4") (pin "162") (pinfunction "PB4_162") (pintype "bidirectional"))
      (node (ref "X1") (pin "4") (pinfunction "1_4") (pintype "passive"))
    )
    (net (code "216") (name "USB_D_N") (class "Default")
      (node (ref "IC11") (pin "1") (pinfunction "IO1_1") (pintype "bidirectional"))
      (node (ref "J2") (pin "2") (pinfunction "D-_2") (pintype "passive"))
      (node (ref "R29") (pin "1") (pinfunction "1_1") (pintype "passive"))
    )
    (net (code "217") (name "USB_D_P") (class "Default")
      (node (ref "IC11") (pin "2") (pinfunction "IO2_2") (pintype "bidirectional"))
      (node (ref "J2") (pin "3") (pinfunction "D+_3") (pintype "passive"))
      (node (ref "R30") (pin "1") (pinfunction "1_1") (pintype "passive"))
    )
    (net (code "218") (name "USB_OTG_FS_D_N") (class "Default")
      (node (ref "IC4") (pin "126") (pinfunction "PA11_126") (pintype "bidirectional"))
      (node (ref "R29") (pin "2") (pinfunction "2_2") (pintype "passive"))
    )
    (net (code "219") (name "USB_OTG_FS_D_P") (class "Default")
      (node (ref "IC4") (pin "127") (pinfunction "PA12_127") (pintype "bidirectional"))
      (node (ref "R30") (pin "2") (pinfunction "2_2") (pintype "passive"))
    )
    (net (code "220") (name "USB_OTG_FS_ID") (class "Default")
      (node (ref "IC11") (pin "4") (pinfunction "IO3_4") (pintype "bidirectional"))
      (node (ref "IC4") (pin "125") (pinfunction "PA10_125") (pintype "bidirectional"))
      (node (ref "J2") (pin "4") (pinfunction "ID_4") (pintype "passive"))
    )
    (net (code "221") (name "USB_OTG_FS_PSO") (class "Default")
      (node (ref "IC4") (pin "147") (pinfunction "PD5_147") (pintype "bidirectional"))
      (node (ref "IC9") (pin "4") (pinfunction "EN_4") (pintype "input"))
    )
    (net (code "222") (name "USB_OTG_FS_VBUS") (class "Default")
      (node (ref "C49") (pin "+") (pinfunction "+_+") (pintype "passive"))
      (node (ref "C52") (pin "2") (pinfunction "2_2") (pintype "passive"))
      (node (ref "IC11") (pin "6") (pinfunction "VCC_6") (pintype "passive"))
      (node (ref "IC4") (pin "124") (pinfunction "PA9_124") (pintype "bidirectional"))
      (node (ref "IC9") (pin "1") (pinfunction "OUT_1") (pintype "output"))
      (node (ref "J2") (pin "1") (pinfunction "VCC_1") (pintype "passive"))
      (node (ref "R28") (pin "1") (pinfunction "1_1") (pintype "passive"))
    )
    (net (code "223") (name "USER_SW") (class "Default")
      (node (ref "C4") (pin "2") (pinfunction "2_2") (pintype "passive"))
      (node (ref "IC4") (pin "152") (pinfunction "PG9_152") (pintype "bidirectional"))
      (node (ref "SW1") (pin "1") (pinfunction "1_1") (pintype "passive"))
    )
    (net (code "224") (name "VBAT") (class "Default")
      (node (ref "IC4") (pin "6") (pinfunction "VBAT_6") (pintype "power_in"))
      (node (ref "JP6") (pin "COM") (pinfunction "COM_COM") (pintype "passive"))
    )
    (net (code "225") (name "VCAP1") (class "Default")
      (node (ref "C37") (pin "1") (pinfunction "1_1") (pintype "passive"))
      (node (ref "IC4") (pin "81") (pinfunction "VCAP_1_81") (pintype "power_in"))
    )
    (net (code "226") (name "VCAP2") (class "Default")
      (node (ref "C36") (pin "1") (pinfunction "1_1") (pintype "passive"))
      (node (ref "IC4") (pin "129") (pinfunction "VCAP_2_129") (pintype "power_in"))
    )
    (net (code "227") (name "VDD") (class "Default")
      (node (ref "C16") (pin "1") (pinfunction "1_1") (pintype "passive"))
      (node (ref "C17") (pin "1") (pinfunction "1_1") (pintype "passive"))
      (node (ref "C18") (pin "1") (pinfunction "1_1") (pintype "passive"))
      (node (ref "C19") (pin "1") (pinfunction "1_1") (pintype "passive"))
      (node (ref "C20") (pin "1") (pinfunction "1_1") (pintype "passive"))
      (node (ref "C21") (pin "1") (pinfunction "1_1") (pintype "passive"))
      (node (ref "C22") (pin "+") (pinfunction "+_+") (pintype "passive"))
      (node (ref "C23") (pin "1") (pinfunction "1_1") (pintype "passive"))
      (node (ref "C24") (pin "1") (pinfunction "1_1") (pintype "passive"))
      (node (ref "C25") (pin "1") (pinfunction "1_1") (pintype "passive"))
      (node (ref "C26") (pin "1") (pinfunction "1_1") (pintype "passive"))
      (node (ref "C27") (pin "1") (pinfunction "1_1") (pintype "passive"))
      (node (ref "C28") (pin "1") (pinfunction "1_1") (pintype "passive"))
      (node (ref "C29") (pin "1") (pinfunction "1_1") (pintype "passive"))
      (node (ref "C30") (pin "1") (pinfunction "1_1") (pintype "passive"))
      (node (ref "C31") (pin "1") (pinfunction "1_1") (pintype "passive"))
      (node (ref "C32") (pin "1") (pinfunction "1_1") (pintype "passive"))
      (node (ref "C33") (pin "1") (pinfunction "1_1") (pintype "passive"))
      (node (ref "FB1") (pin "P$1") (pinfunction "1_P$1") (pintype "passive"))
      (node (ref "IC4") (pin "118") (pinfunction "VDDUSB_118") (pintype "power_in"))
      (node (ref "IC4") (pin "131") (pinfunction "VDD_10_131") (pintype "power_in"))
      (node (ref "IC4") (pin "136") (pinfunction "VDD_11_136") (pintype "power_in"))
      (node (ref "IC4") (pin "149") (pinfunction "VDDSDMMC_149") (pintype "power_in"))
      (node (ref "IC4") (pin "15") (pinfunction "VDD_2_15") (pintype "power_in"))
      (node (ref "IC4") (pin "159") (pinfunction "VDD_12_159") (pintype "power_in"))
      (node (ref "IC4") (pin "171") (pinfunction "PDR_ON_171") (pintype "passive"))
      (node (ref "IC4") (pin "172") (pinfunction "VDD_172") (pintype "power_in"))
      (node (ref "IC4") (pin "23") (pinfunction "VDD_3_23") (pintype "power_in"))
      (node (ref "IC4") (pin "36") (pinfunction "VDD_4_36") (pintype "power_in"))
      (node (ref "IC4") (pin "49") (pinfunction "VDD_5_49") (pintype "power_in"))
      (node (ref "IC4") (pin "62") (pinfunction "VDD_6_62") (pintype "power_in"))
      (node (ref "IC4") (pin "72") (pinfunction "VDD_7_72") (pintype "power_in"))
      (node (ref "IC4") (pin "82") (pinfunction "VDD_8_82") (pintype "power_in"))
      (node (ref "IC4") (pin "96") (pinfunction "VDD_9_96") (pintype "power_in"))
      (node (ref "IC4") (pin "99") (pinfunction "VDDDSI_99") (pintype "power_in"))
      (node (ref "JP4") (pin "1") (pinfunction "1_1") (pintype "passive"))
      (node (ref "JP6") (pin "NO") (pinfunction "NO_NO") (pintype "passive"))
      (node (ref "R11") (pin "1") (pinfunction "1_1") (pintype "passive"))
    )
    (net (code "228") (name "VDDA") (class "Default")
      (node (ref "C34") (pin "1") (pinfunction "1_1") (pintype "passive"))
      (node (ref "C35") (pin "1") (pinfunction "1_1") (pintype "passive"))
      (node (ref "FB1") (pin "P$2") (pinfunction "2_P$2") (pintype "passive"))
      (node (ref "IC4") (pin "39") (pinfunction "VDDA_39") (pintype "power_in"))
      (node (ref "R17") (pin "2") (pinfunction "2_2") (pintype "passive"))
    )
    (net (code "229") (name "VLED+") (class "Default")
      (node (ref "C48") (pin "1") (pinfunction "1_1") (pintype "passive"))
      (node (ref "D2") (pin "C") (pinfunction "C_C") (pintype "passive"))
      (node (ref "LCD1") (pin "2") (pinfunction "VLED+_2") (pintype "power_in"))
      (node (ref "ZD3") (pin "C") (pinfunction "C_C") (pintype "passive"))
    )
    (net (code "230") (name "VLED-") (class "Default")
      (node (ref "IC10") (pin "3") (pinfunction "FB_3") (pintype "input"))
      (node (ref "LCD1") (pin "1") (pinfunction "VLED-_1") (pintype "power_in"))
      (node (ref "R26") (pin "1") (pinfunction "1_1") (pintype "passive"))
      (node (ref "ZD3") (pin "A") (pinfunction "A_A") (pintype "passive"))
    )
    (net (code "231") (name "VREF+") (class "Default")
      (node (ref "IC4") (pin "38") (pinfunction "VREF+_38") (pintype "power_in"))
      (node (ref "R17") (pin "1") (pinfunction "1_1") (pintype "passive"))
    )
    (net (code "232") (name "XL") (class "Default")
      (node (ref "IC13") (pin "4") (pinfunction "IO3_4") (pintype "bidirectional"))
      (node (ref "IC14") (pin "4") (pinfunction "X-_4") (pintype "input"))
      (node (ref "LCD1") (pin "39") (pinfunction "XL_39") (pintype "passive"))
    )
    (net (code "233") (name "XR") (class "Default")
      (node (ref "IC13") (pin "1") (pinfunction "IO1_1") (pintype "bidirectional"))
      (node (ref "IC14") (pin "2") (pinfunction "X+_2") (pintype "input"))
      (node (ref "LCD1") (pin "37") (pinfunction "XR_37") (pintype "passive"))
    )
    (net (code "234") (name "YD") (class "Default")
      (node (ref "IC13") (pin "2") (pinfunction "IO2_2") (pintype "bidirectional"))
      (node (ref "IC14") (pin "5") (pinfunction "Y-_5") (pintype "input"))
      (node (ref "LCD1") (pin "38") (pinfunction "YD_38") (pintype "passive"))
    )
    (net (code "235") (name "YU") (class "Default")
      (node (ref "IC13") (pin "5") (pinfunction "IO4_5") (pintype "bidirectional"))
      (node (ref "IC14") (pin "3") (pinfunction "Y+_3") (pintype "input"))
      (node (ref "LCD1") (pin "40") (pinfunction "YU_40") (pintype "passive"))
    )
    (net (code "236") (name "unconnected-(IC4C-DSI_CKN-Pad105)") (class "Default")
      (node (ref "IC4") (pin "105") (pinfunction "DSI_CKN_105") (pintype "bidirectional"))
    )
    (net (code "237") (name "unconnected-(IC4C-DSI_CKP-Pad104)") (class "Default")
      (node (ref "IC4") (pin "104") (pinfunction "DSI_CKP_104") (pintype "bidirectional"))
    )
    (net (code "238") (name "unconnected-(IC4C-DSI_D0N-Pad102)") (class "Default")
      (node (ref "IC4") (pin "102") (pinfunction "DSI_D0N_102") (pintype "bidirectional"))
    )
    (net (code "239") (name "unconnected-(IC4C-DSI_D0P-Pad101)") (class "Default")
      (node (ref "IC4") (pin "101") (pinfunction "DSI_D0P_101") (pintype "bidirectional"))
    )
    (net (code "240") (name "unconnected-(IC4C-DSI_D1N-Pad108)") (class "Default")
      (node (ref "IC4") (pin "108") (pinfunction "DSI_D1N_108") (pintype "bidirectional"))
    )
    (net (code "241") (name "unconnected-(IC4C-DSI_D1P-Pad107)") (class "Default")
      (node (ref "IC4") (pin "107") (pinfunction "DSI_D1P_107") (pintype "bidirectional"))
    )
    (net (code "242") (name "unconnected-(IC4C-PI8-Pad7)") (class "Default")
      (node (ref "IC4") (pin "7") (pinfunction "PI8_7") (pintype "bidirectional"))
    )
    (net (code "243") (name "unconnected-(IC7-A12{slash}NC-36-Pad36)") (class "Default")
      (node (ref "IC7") (pin "36") (pinfunction "A12/NC-36_36") (pintype "passive"))
    )
    (net (code "244") (name "unconnected-(IC7-NC-40-Pad40)") (class "Default")
      (node (ref "IC7") (pin "40") (pinfunction "NC-40_40") (pintype "no_connect"))
    )
    (net (code "245") (name "unconnected-(IC11-IO4-Pad5)") (class "Default")
      (node (ref "IC11") (pin "5") (pinfunction "IO4_5") (pintype "bidirectional"))
    )
    (net (code "246") (name "unconnected-(IC14-AUX-Pad16)") (class "Default")
      (node (ref "IC14") (pin "16") (pinfunction "AUX_16") (pintype "input"))
    )
    (net (code "247") (name "unconnected-(IC16-CLK_OUT-Pad25)") (class "Default")
      (node (ref "IC16") (pin "25") (pinfunction "CLK_OUT_25") (pintype "output"))
    )
    (net (code "248") (name "unconnected-(IC16-TCK-Pad8)") (class "Default")
      (node (ref "IC16") (pin "8") (pinfunction "TCK_8") (pintype "input"))
    )
    (net (code "249") (name "unconnected-(IC16-TDI-Pad12)") (class "Default")
      (node (ref "IC16") (pin "12") (pinfunction "TDI_12") (pintype "input"))
    )
    (net (code "250") (name "unconnected-(IC16-TDO-Pad9)") (class "Default")
      (node (ref "IC16") (pin "9") (pinfunction "TDO_9") (pintype "output"))
    )
    (net (code "251") (name "unconnected-(IC16-TMS-Pad10)") (class "Default")
      (node (ref "IC16") (pin "10") (pinfunction "TMS_10") (pintype "input"))
    )
    (net (code "252") (name "unconnected-(IC16-X2-Pad33)") (class "Default")
      (node (ref "IC16") (pin "33") (pinfunction "X2_33") (pintype "output"))
    )
    (net (code "253") (name "unconnected-(IC16-~{TRST}-Pad11)") (class "Default")
      (node (ref "IC16") (pin "11") (pinfunction "~{TRST}_11") (pintype "input"))
    )
    (net (code "254") (name "unconnected-(J1-CD{slash}DAT3-Pad2)") (class "Default")
      (node (ref "J1") (pin "2") (pinfunction "CD/DAT3_2") (pintype "passive"))
    )
    (net (code "255") (name "unconnected-(J1-DAT1-Pad8)") (class "Default")
      (node (ref "J1") (pin "8") (pinfunction "DAT1_8") (pintype "passive"))
    )
    (net (code "256") (name "unconnected-(J1-DAT2-Pad1)") (class "Default")
      (node (ref "J1") (pin "1") (pinfunction "DAT2_1") (pintype "passive"))
    )
    (net (code "257") (name "unconnected-(LCD1-NC1-Pad35)") (class "Default")
      (node (ref "LCD1") (pin "35") (pinfunction "NC1_35") (pintype "no_connect"))
    )
    (net (code "258") (name "~{FAULT}") (class "Default")
      (node (ref "IC3") (pin "1") (pinfunction "~{FAULT}_1") (pintype "output"))
      (node (ref "IC4") (pin "58") (pinfunction "PB2_58") (pintype "bidirectional"))
      (node (ref "R14") (pin "2") (pinfunction "2_2") (pintype "passive"))
      (node (ref "X1") (pin "8") (pinfunction "1_8") (pintype "passive"))
      (node (ref "X2") (pin "15") (pinfunction "1_15") (pintype "passive"))
    )
    (net (code "259") (name "~{RESET}") (class "Default")
      (node (ref "IC16") (pin "29") (pinfunction "RESET_N_29") (pintype "input"))
      (node (ref "IC3") (pin "4") (pinfunction "ENA_4") (pintype "input"))
      (node (ref "IC4") (pin "31") (pinfunction "NRST_31") (pintype "bidirectional"))
      (node (ref "IC6") (pin "4") (pinfunction "IO3_4") (pintype "bidirectional"))
      (node (ref "JP9") (pin "NO") (pinfunction "NO_NO") (pintype "passive"))
      (node (ref "R11") (pin "2") (pinfunction "2_2") (pintype "passive"))
      (node (ref "X1") (pin "6") (pinfunction "1_6") (pintype "passive"))
      (node (ref "X4") (pin "5") (pinfunction "S_5") (pintype "passive"))
    )
    (net (code "260") (name "~{USB_OTG_FS_OC}") (class "Default")
      (node (ref "IC4") (pin "146") (pinfunction "PD4_146") (pintype "bidirectional"))
      (node (ref "IC9") (pin "3") (pinfunction "~{OC}_3") (pintype "passive"))
      (node (ref "R27") (pin "1") (pinfunction "1_1") (pintype "passive"))
    )
  )
)
